# Arduino101.net
KiCad netlist of a schematic drawn in EAGLE
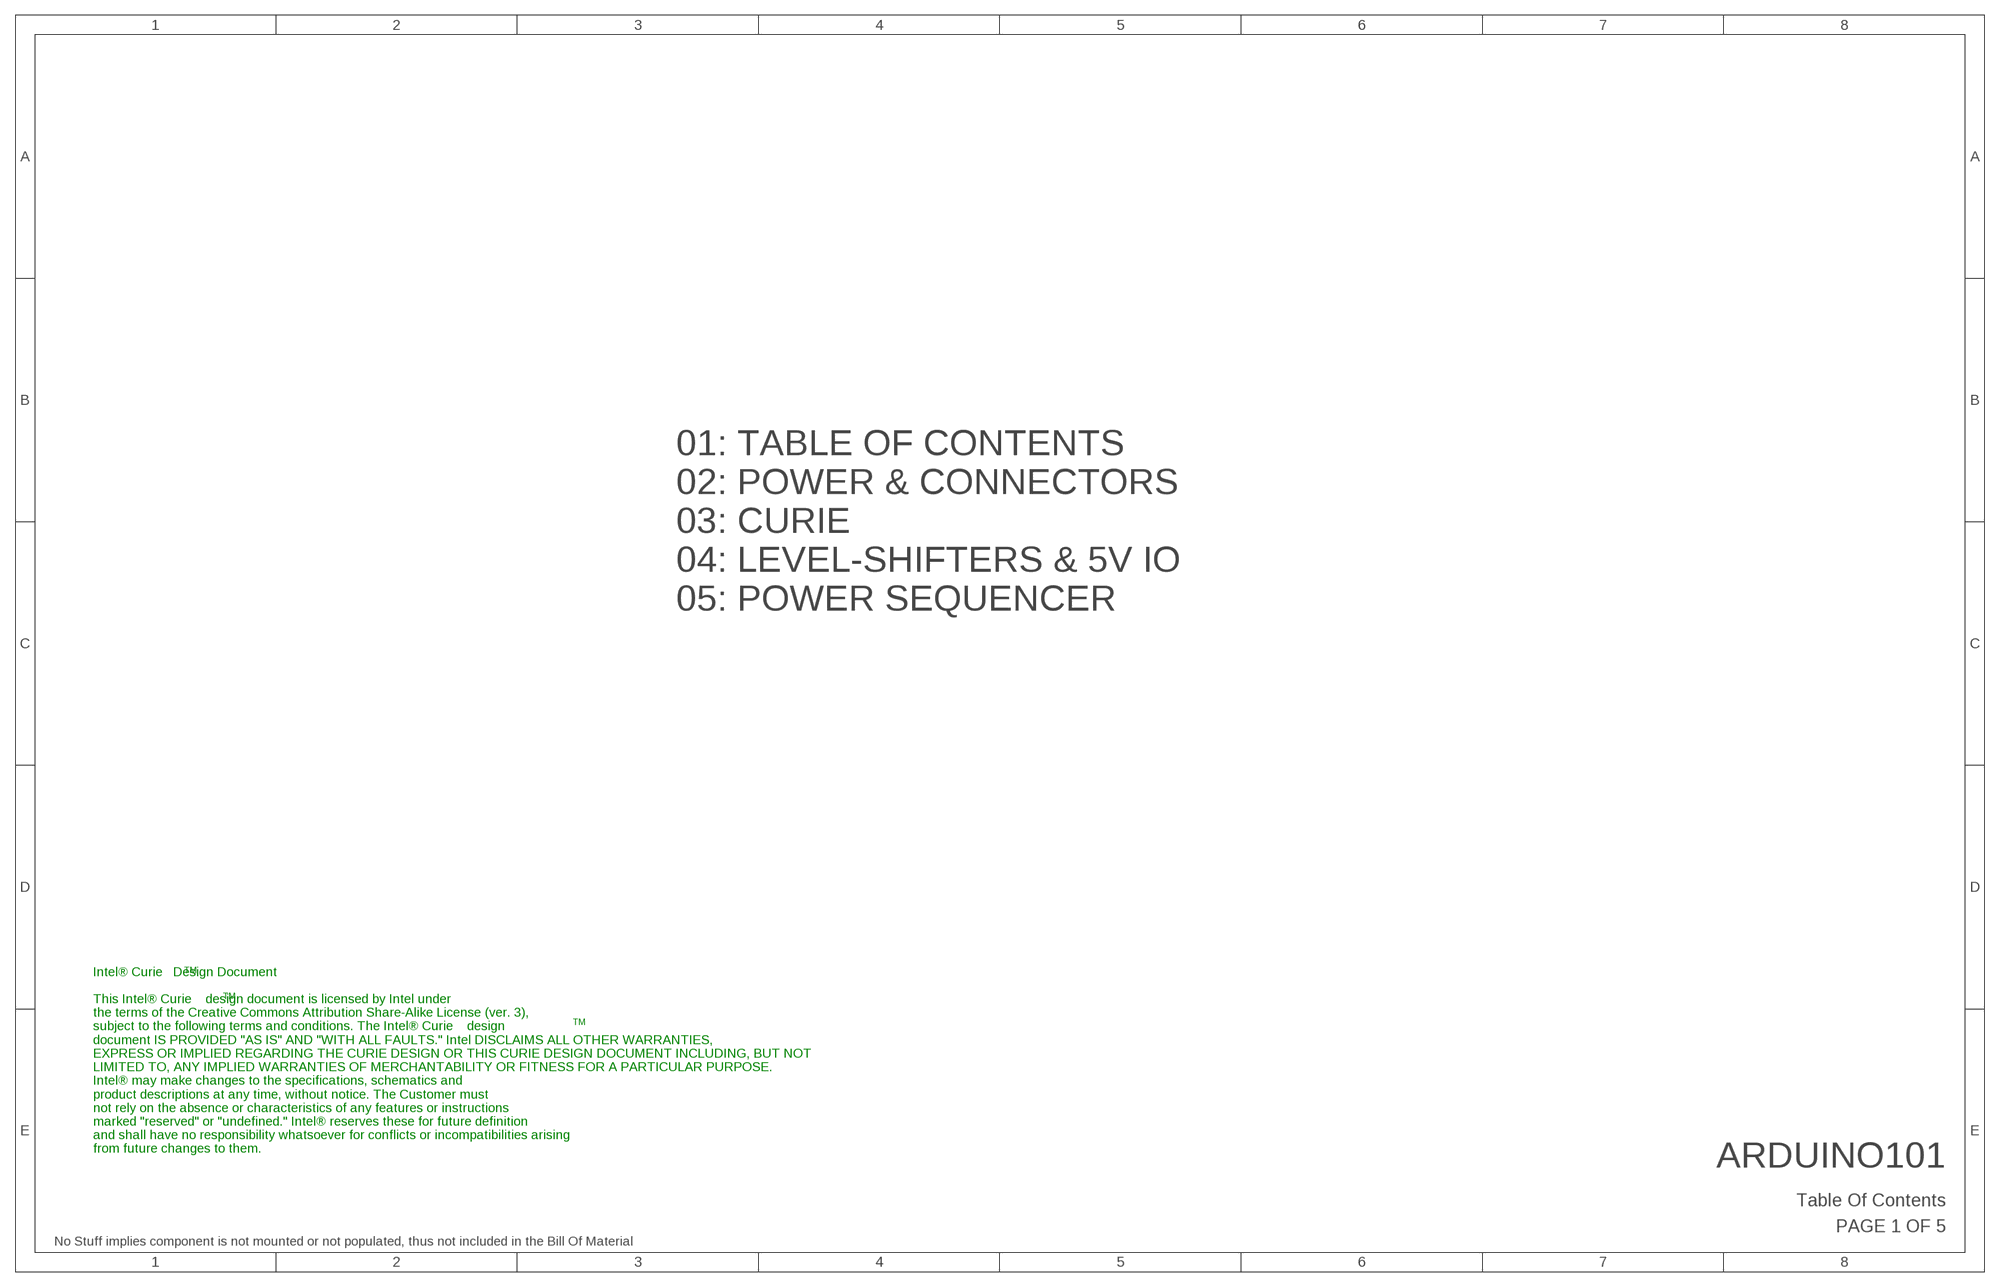
[diagram p0: schematic, sheet 1]
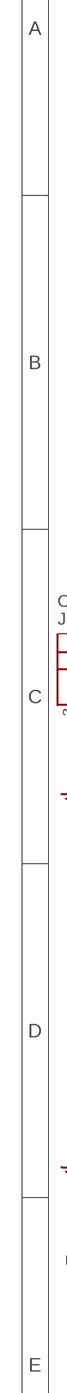
[diagram p1: schematic, sheet 2, part 1 of 2]
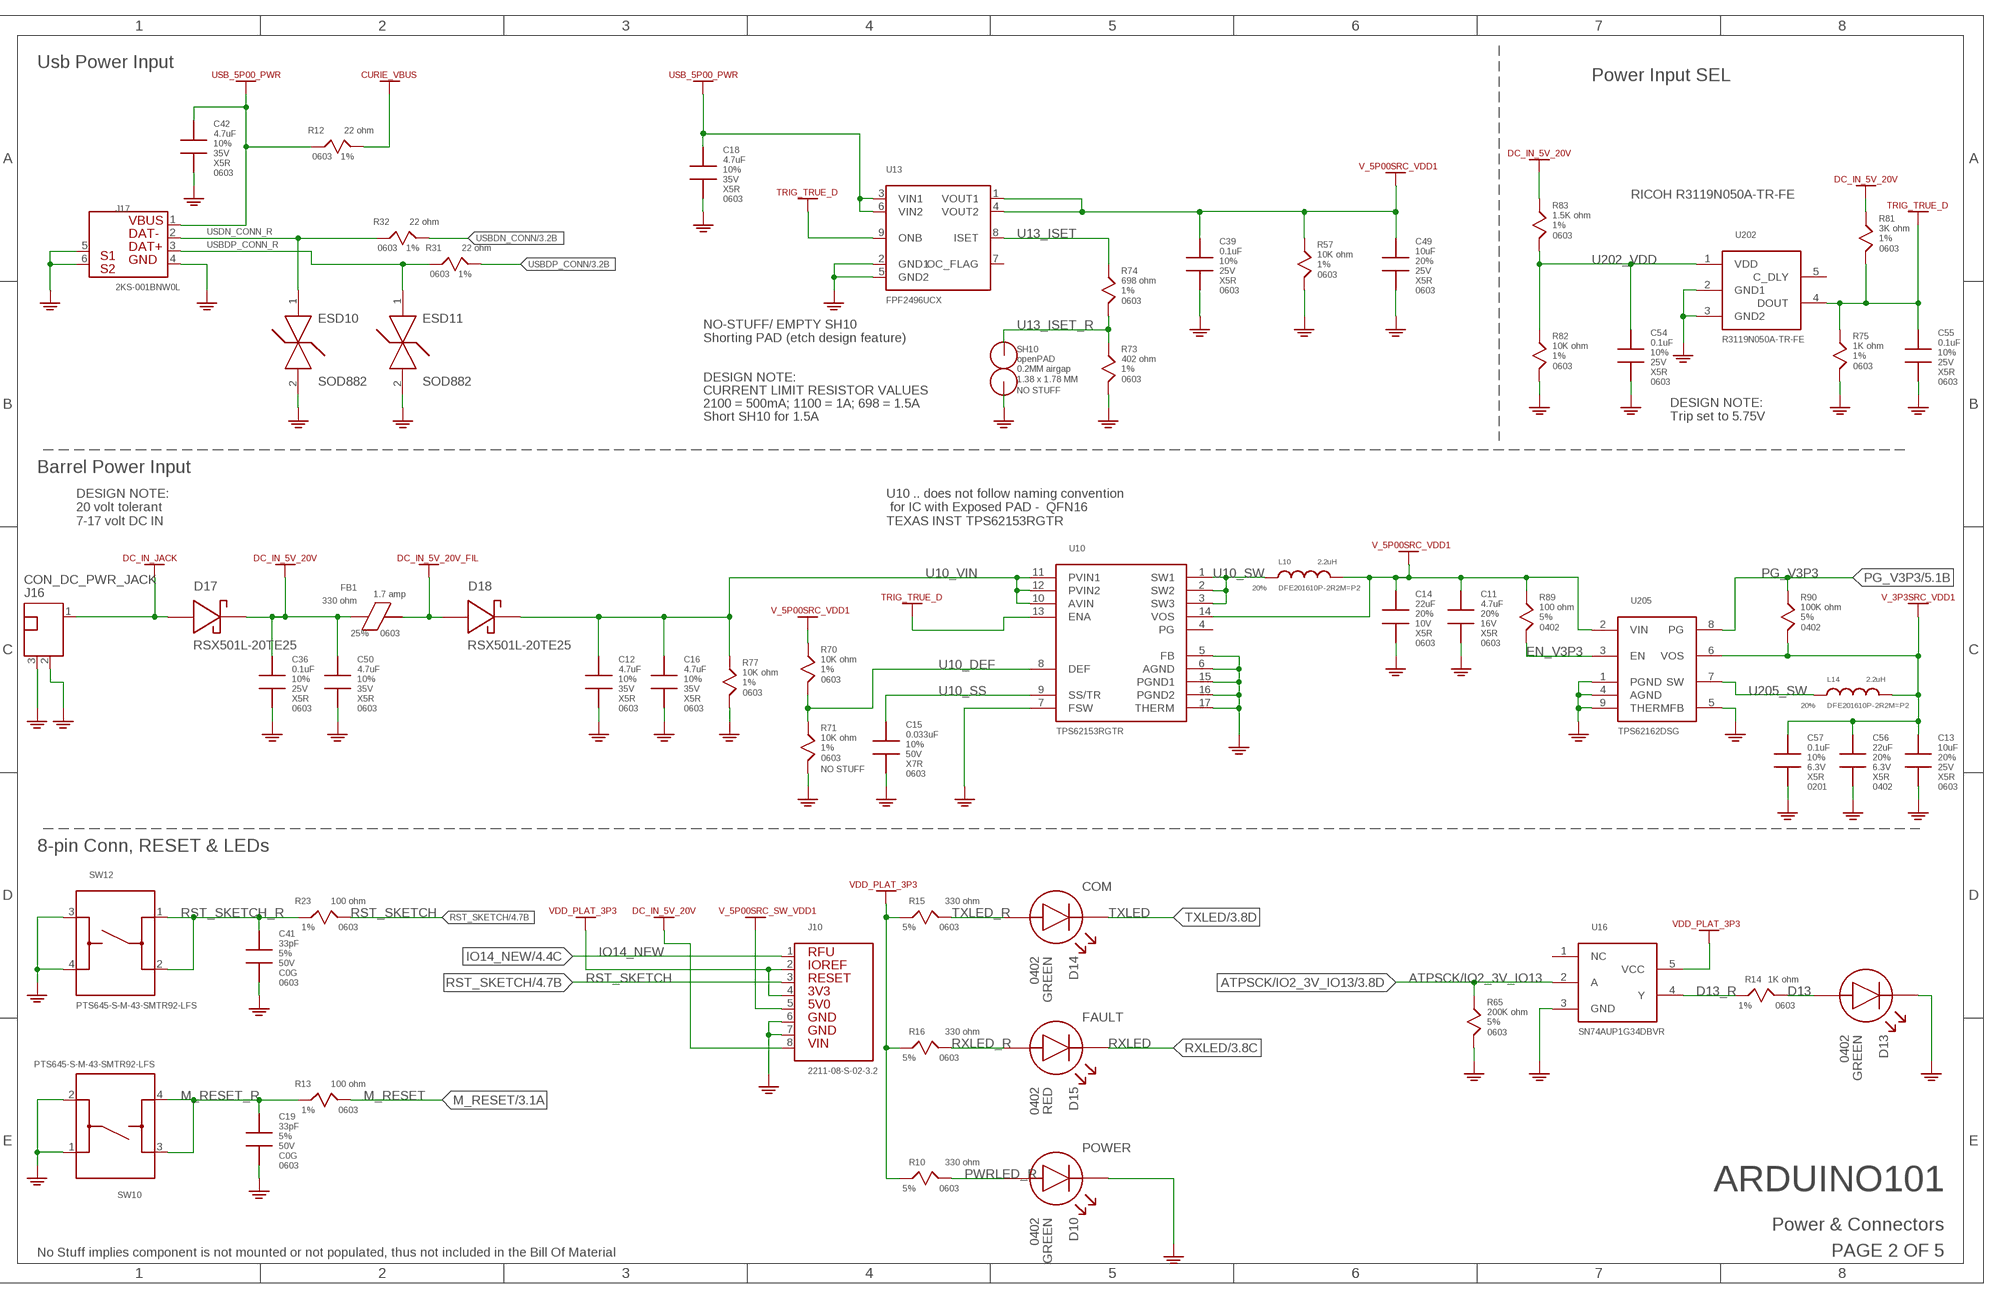
[diagram p2: schematic, sheet 2, part 2 of 2]
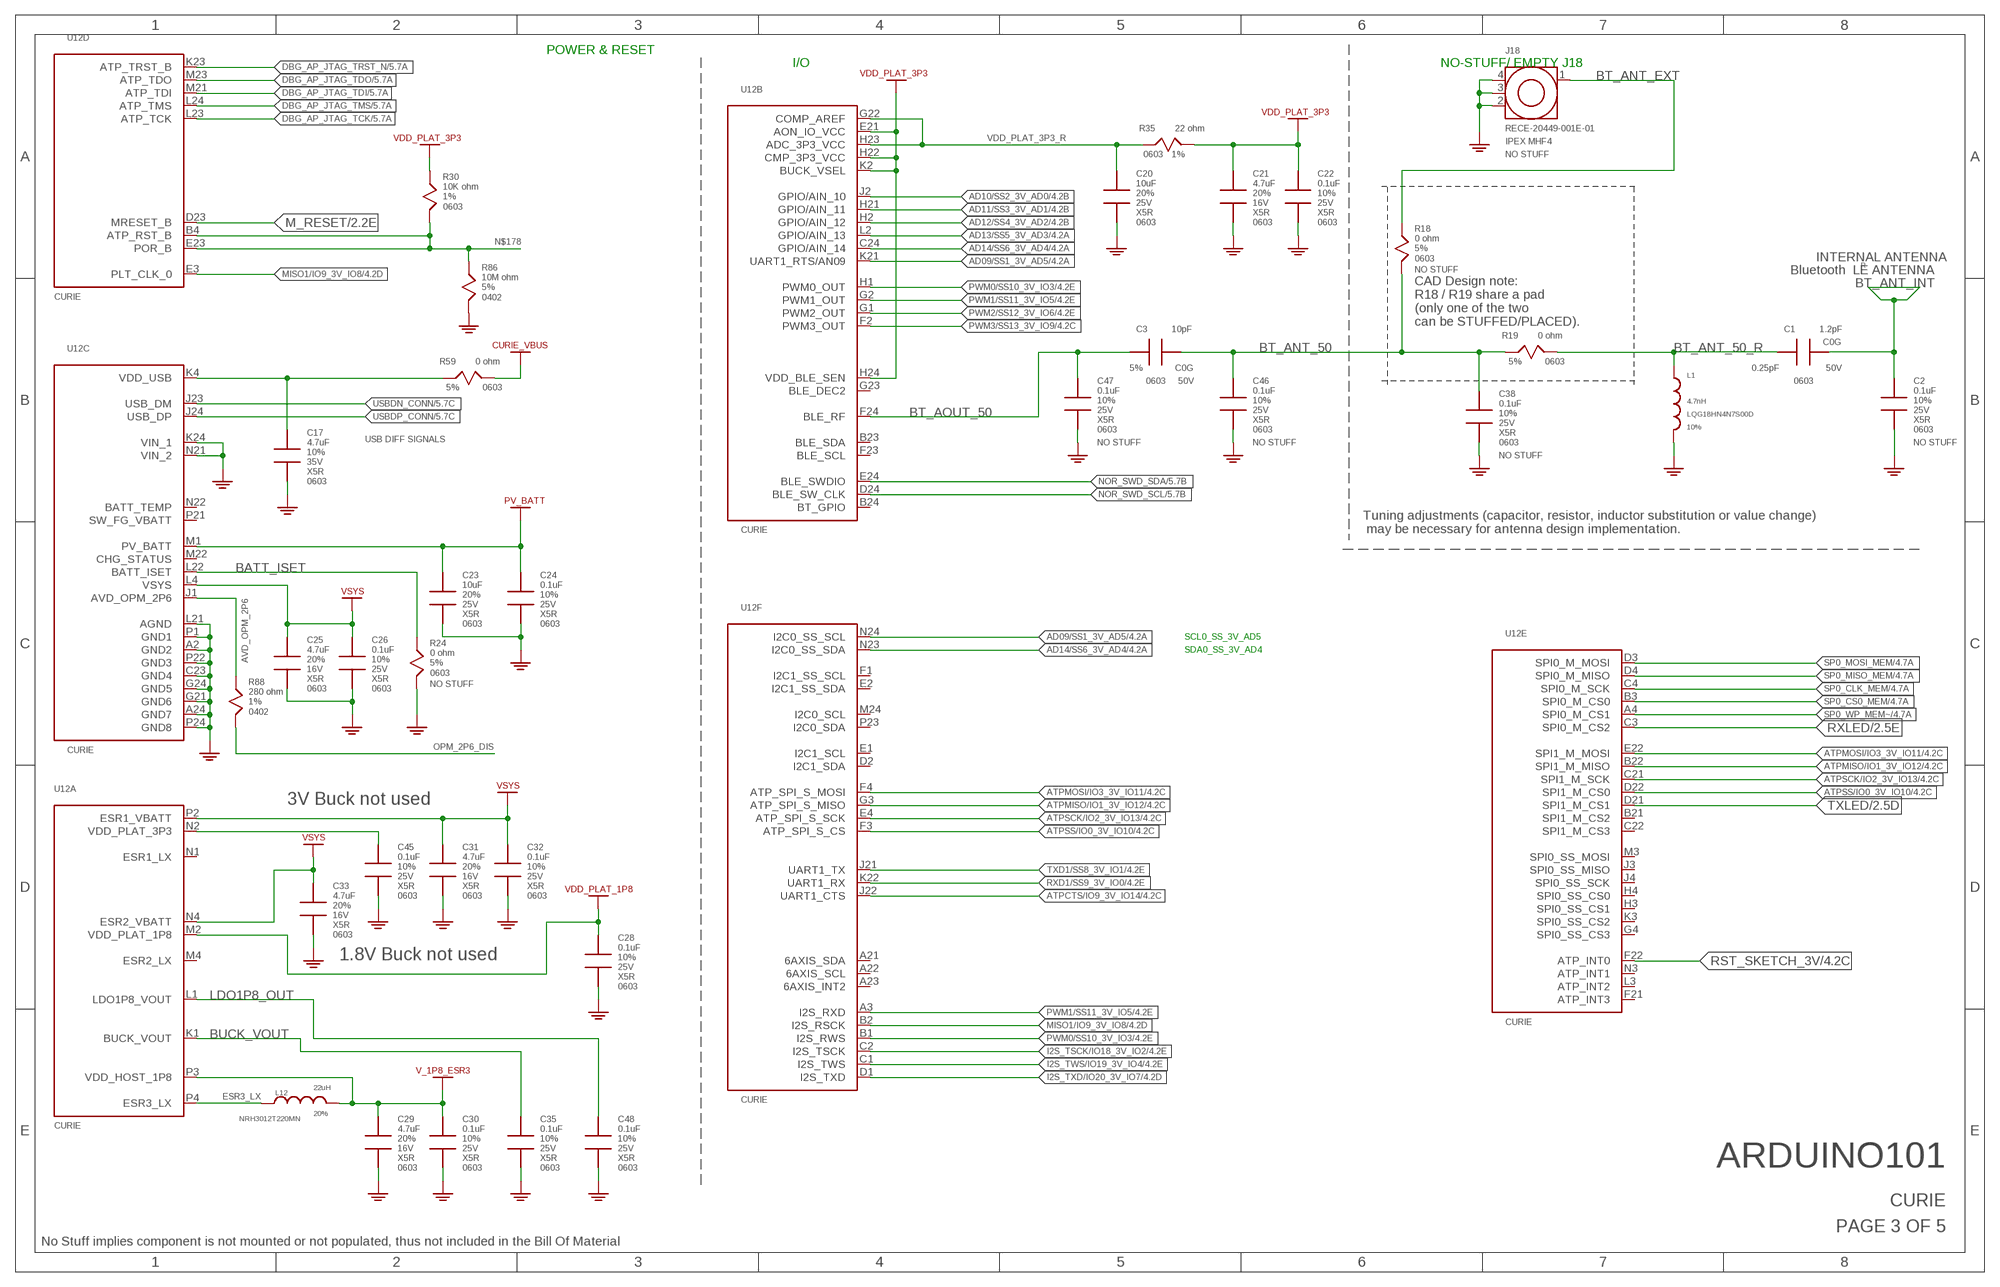
[diagram p3: schematic, sheet 3]
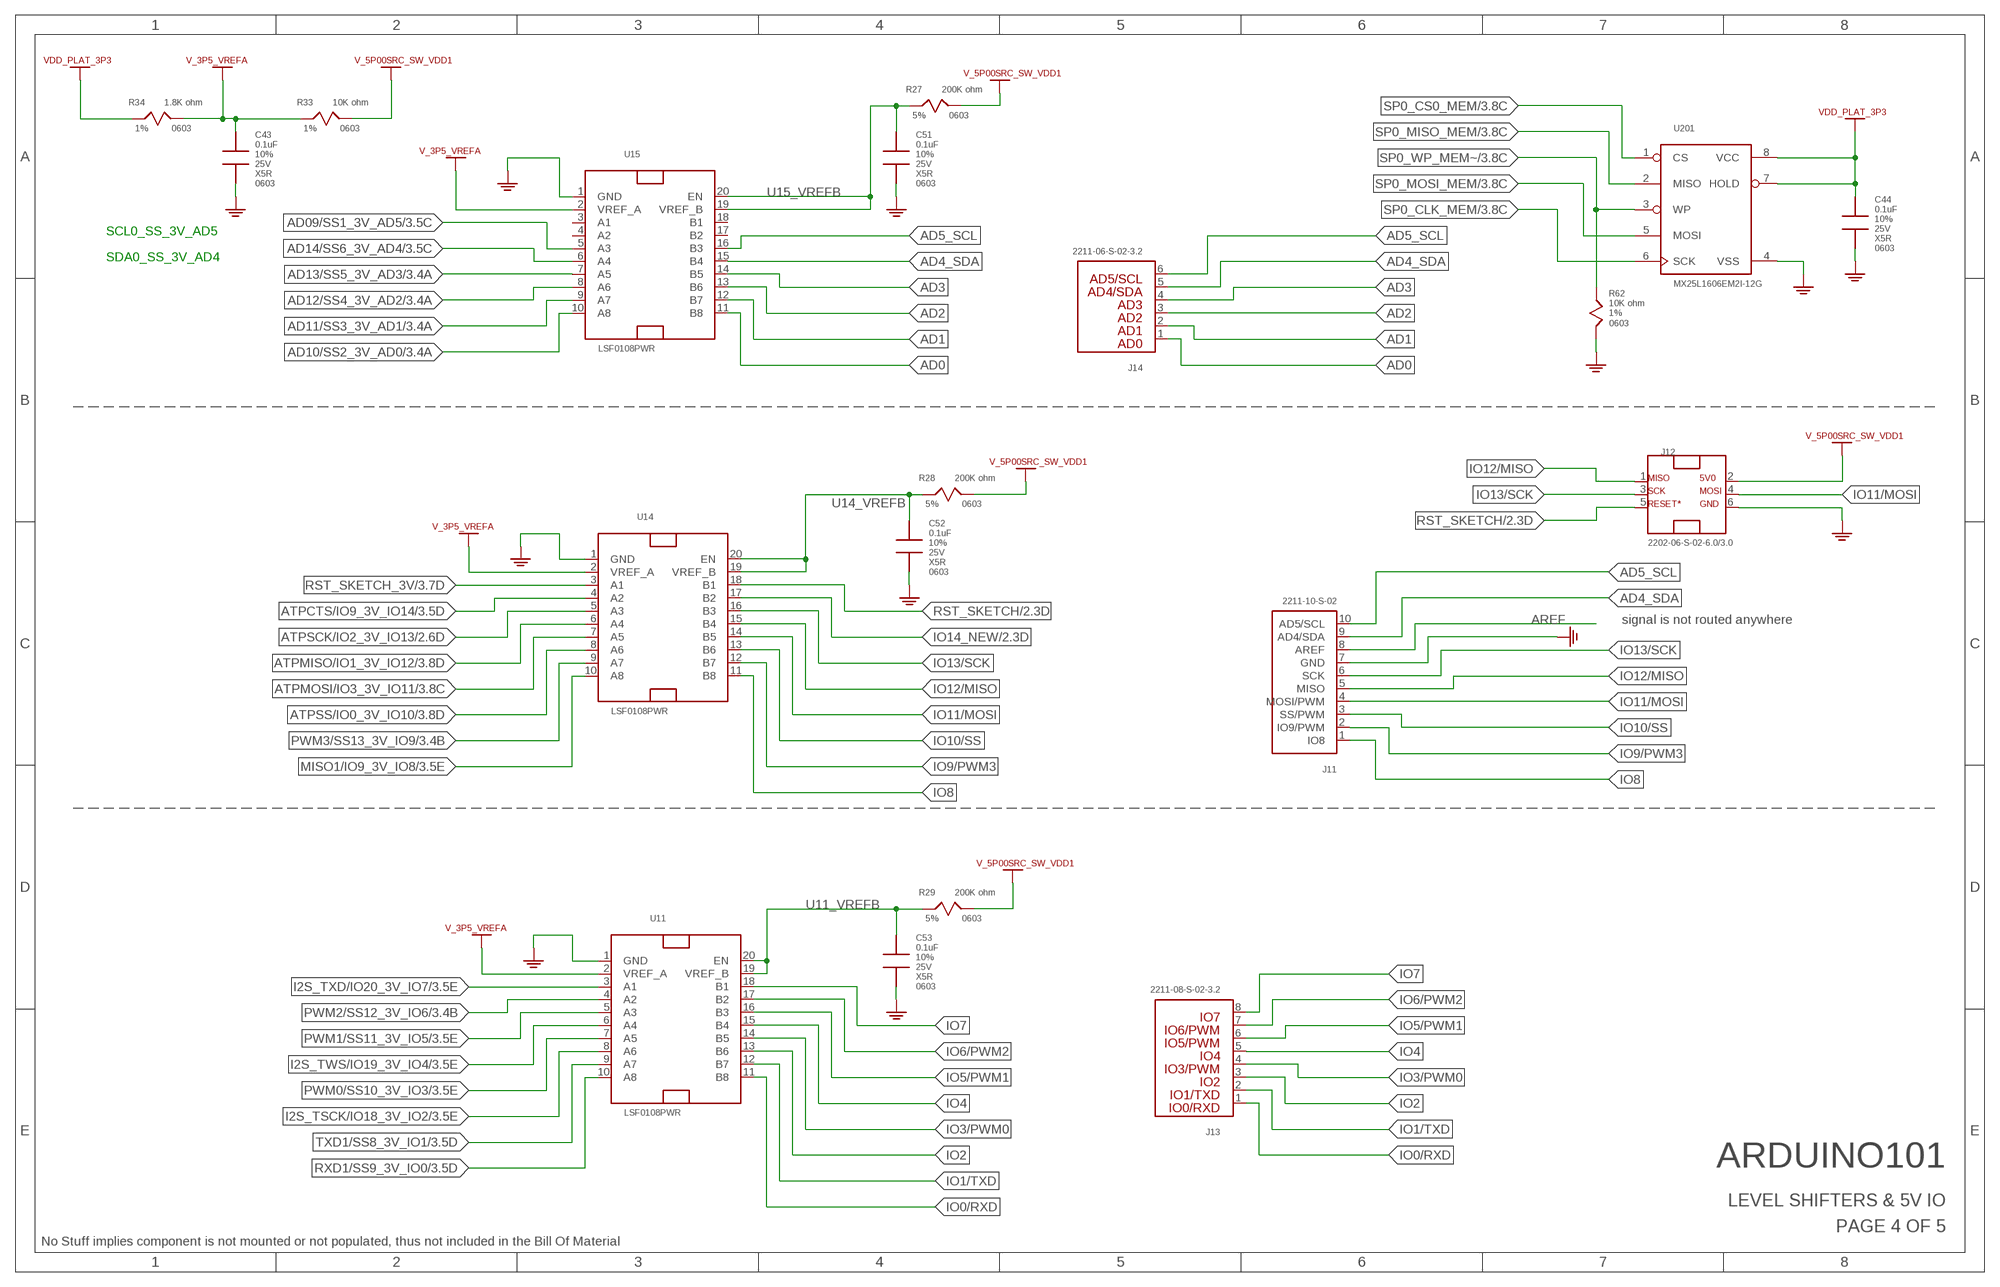
[diagram p4: schematic, sheet 4]
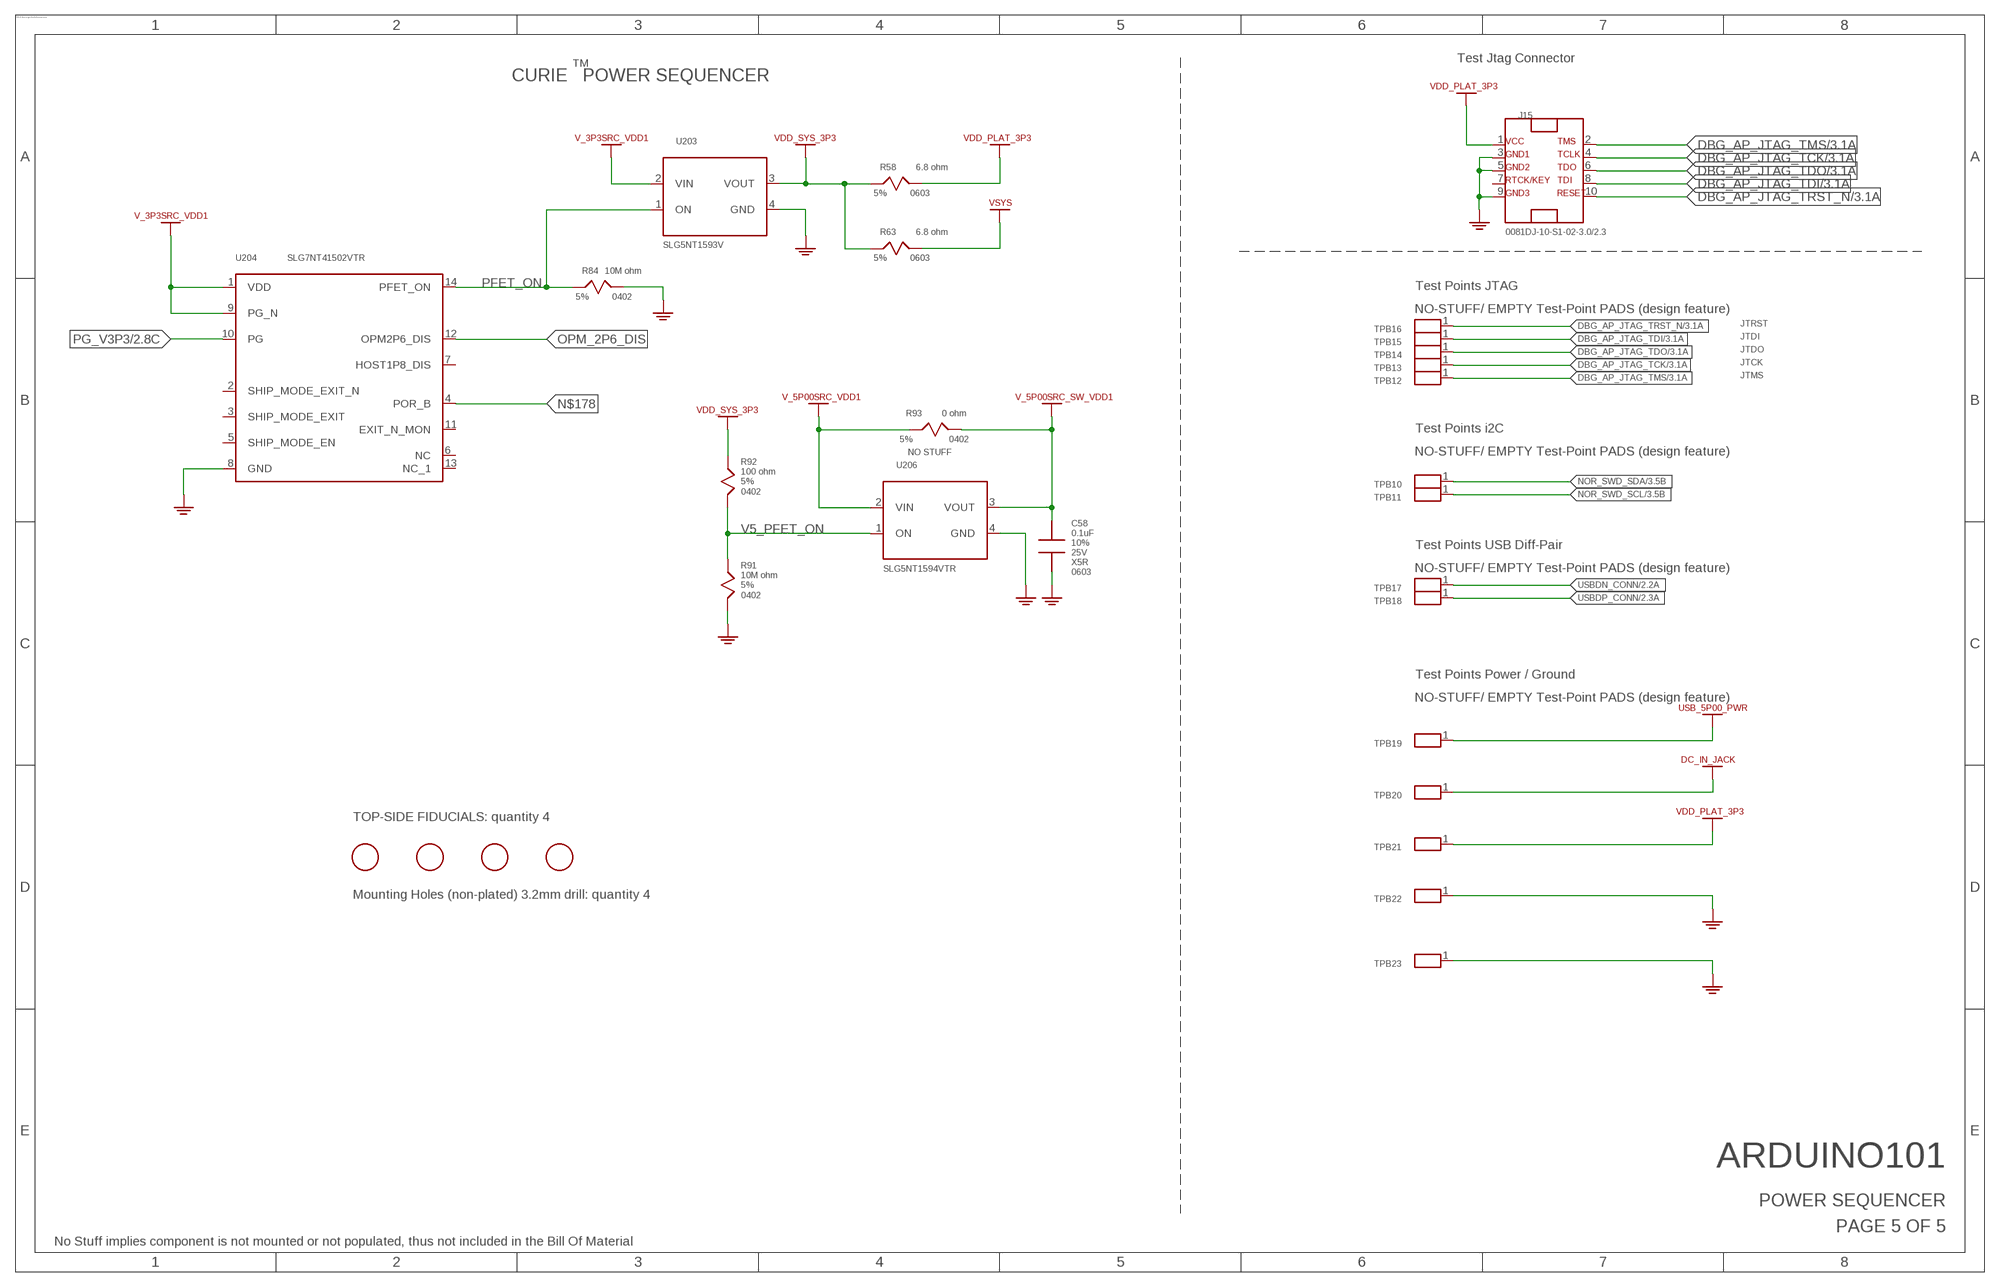
[diagram p5: schematic, sheet 5]

(export (version "E")
  (design (tool "Eeschema 10.0.6"))
  (components
    (comp (ref "C11")
      (value "4.7uF")
      (footprint "eagle-import:0603X90H")
      (fields (field (name "VOLTAGE") "16V") (field (name "MANUFACTURER") "MURATA"))
      (libsource (lib "eagle-import") (part "GRM188R61C475KAAJD"))
    )
    (comp (ref "C12")
      (value "4.7uF")
      (footprint "eagle-import:0603X90H")
      (fields (field (name "VOLTAGE") "35V") (field (name "MANUFACTURER") "MURATA"))
      (libsource (lib "eagle-import") (part "GRM188R6YA475KE15D"))
    )
    (comp (ref "C13")
      (value "10uF")
      (footprint "eagle-import:0603X90H")
      (fields (field (name "VOLTAGE") "25V") (field (name "MANUFACTURER") "MURATA"))
      (libsource (lib "eagle-import") (part "GRM188R61E106MA73D"))
    )
    (comp (ref "C14")
      (value "22uF")
      (footprint "eagle-import:0603X90H")
      (fields (field (name "VOLTAGE") "10V") (field (name "MANUFACTURER") "MURATA"))
      (libsource (lib "eagle-import") (part "GRM188R61A226ME15D"))
    )
    (comp (ref "C15")
      (value "0.033uF")
      (footprint "eagle-import:0603X90H")
      (fields (field (name "VOLTAGE") "50V") (field (name "MANUFACTURER") "MURATA"))
      (libsource (lib "eagle-import") (part "GRM188R71H333KA61F"))
    )
    (comp (ref "C16")
      (value "4.7uF")
      (footprint "eagle-import:0603X90H")
      (fields (field (name "VOLTAGE") "35V") (field (name "MANUFACTURER") "MURATA"))
      (libsource (lib "eagle-import") (part "GRM188R6YA475KE15D"))
    )
    (comp (ref "C18")
      (value "4.7uF")
      (footprint "eagle-import:0603X90H")
      (fields (field (name "VOLTAGE") "35V") (field (name "MANUFACTURER") "MURATA"))
      (libsource (lib "eagle-import") (part "GRM188R6YA475KE15D"))
    )
    (comp (ref "C19")
      (value "33pF")
      (footprint "eagle-import:0603X90H")
      (fields (field (name "VOLTAGE") "50V") (field (name "MANUFACTURER") "MURATA"))
      (libsource (lib "eagle-import") (part "GRM1885C1H330JA01F"))
    )
    (comp (ref "C36")
      (value "0.1uF")
      (footprint "eagle-import:0603X90H")
      (fields (field (name "VOLTAGE") "25V") (field (name "MANUFACTURER") "MURATA"))
      (libsource (lib "eagle-import") (part "GRM188R61E104KA01"))
    )
    (comp (ref "C39")
      (value "0.1uF")
      (footprint "eagle-import:0603X90H")
      (fields (field (name "VOLTAGE") "25V") (field (name "MANUFACTURER") "MURATA"))
      (libsource (lib "eagle-import") (part "GRM188R61E104KA01"))
    )
    (comp (ref "C41")
      (value "33pF")
      (footprint "eagle-import:0603X90H")
      (fields (field (name "VOLTAGE") "50V") (field (name "MANUFACTURER") "MURATA"))
      (libsource (lib "eagle-import") (part "GRM1885C1H330JA01F"))
    )
    (comp (ref "C42")
      (value "4.7uF")
      (footprint "eagle-import:0603X90H")
      (fields (field (name "VOLTAGE") "35V") (field (name "MANUFACTURER") "MURATA"))
      (libsource (lib "eagle-import") (part "GRM188R6YA475KE15D"))
    )
    (comp (ref "C49")
      (value "10uF")
      (footprint "eagle-import:0603X90H")
      (fields (field (name "VOLTAGE") "25V") (field (name "MANUFACTURER") "MURATA"))
      (libsource (lib "eagle-import") (part "GRM188R61E106MA73D"))
    )
    (comp (ref "C50")
      (value "4.7uF")
      (footprint "eagle-import:0603X90H")
      (fields (field (name "VOLTAGE") "35V") (field (name "MANUFACTURER") "MURATA"))
      (libsource (lib "eagle-import") (part "GRM188R6YA475KE15D"))
    )
    (comp (ref "C54")
      (value "0.1uF")
      (footprint "eagle-import:0603X90H")
      (fields (field (name "VOLTAGE") "25V") (field (name "MANUFACTURER") "MURATA"))
      (libsource (lib "eagle-import") (part "GRM188R61E104KA01"))
    )
    (comp (ref "C55")
      (value "0.1uF")
      (footprint "eagle-import:0603X90H")
      (fields (field (name "VOLTAGE") "25V") (field (name "MANUFACTURER") "MURATA"))
      (libsource (lib "eagle-import") (part "GRM188R61E104KA01"))
    )
    (comp (ref "C56")
      (value "22uF")
      (footprint "eagle-import:CAP0402")
      (fields (field (name "VOLTAGE") "6.3V") (field (name "MANUFACTURER") "MURATA"))
      (libsource (lib "eagle-import") (part "GRM155R60J226ME11D"))
    )
    (comp (ref "C57")
      (value "0.1uF")
      (footprint "eagle-import:CAP0201")
      (fields (field (name "VOLTAGE") "6.3V") (field (name "MANUFACTURER") "MURATA"))
      (libsource (lib "eagle-import") (part "GRM033R60J104KE81D"))
    )
    (comp (ref "D10")
      (value "LED_SML-P12PTT86")
      (footprint "eagle-import:LED_100X60X25H_SMLP13")
      (fields (field (name "MANUFACTURER") "ROHM"))
      (libsource (lib "eagle-import") (part "LED_SML-P12PTT86"))
    )
    (comp (ref "D13")
      (value "LED_SML-P12PTT86")
      (footprint "eagle-import:LED_100X60X25H_SMLP13")
      (fields (field (name "MANUFACTURER") "ROHM"))
      (libsource (lib "eagle-import") (part "LED_SML-P12PTT86"))
    )
    (comp (ref "D14")
      (value "LED_SML-P12PTT86")
      (footprint "eagle-import:LED_100X60X25H_SMLP13")
      (fields (field (name "MANUFACTURER") "ROHM"))
      (libsource (lib "eagle-import") (part "LED_SML-P12PTT86"))
    )
    (comp (ref "D15")
      (value "LED_SML-P11UTT86")
      (footprint "eagle-import:LED_100X60X25H_SMLP13")
      (fields (field (name "MANUFACTURER") "ROHM"))
      (libsource (lib "eagle-import") (part "LED_SML-P11UTT86"))
    )
    (comp (ref "D17")
      (value "DIO_RSX501L-20TE25")
      (footprint "eagle-import:DIO2_450X260X220H")
      (fields (field (name "MANUFACTURER") "ROHM CO"))
      (libsource (lib "eagle-import") (part "DIO_RSX501L-20TE25"))
    )
    (comp (ref "D18")
      (value "DIO_RSX501L-20TE25")
      (footprint "eagle-import:DIO2_450X260X220H")
      (fields (field (name "MANUFACTURER") "ROHM CO"))
      (libsource (lib "eagle-import") (part "DIO_RSX501L-20TE25"))
    )
    (comp (ref "ESD10")
      (value "PESD5V0X1BCAL,315")
      (footprint "eagle-import:DIO_SOD882")
      (fields (field (name "MANUFACTURER") "NXP Semiconductors"))
      (libsource (lib "eagle-import") (part "PESD5V0X1BCAL,315"))
    )
    (comp (ref "ESD11")
      (value "PESD5V0X1BCAL,315")
      (footprint "eagle-import:DIO_SOD882")
      (fields (field (name "MANUFACTURER") "NXP Semiconductors"))
      (libsource (lib "eagle-import") (part "PESD5V0X1BCAL,315"))
    )
    (comp (ref "FB1")
      (value "FERRITE_BEAD_0603_BLM18KG331SN1D")
      (footprint "eagle-import:0603X90H")
      (fields
        (field (name "TOL") "25%")
        (field (name "IMPEDANCE") "330 ohm")
        (field (name "SIZE") "0603")
        (field (name "MANUFACTURER") "MURATA")
      )
      (libsource (lib "eagle-import") (part "FERRITE_BEAD_0603_BLM18KG331SN1D"))
    )
    (comp (ref "J10")
      (value "CON_1X8_2211-08-S-02-3.2")
      (footprint "eagle-import:CONF1X8-254P_2104X240X850H_TH")
      (fields (field (name "MANUFACTURER") "SINGATRON"))
      (libsource (lib "eagle-import") (part "CON_1X8_2211-08-S-02-3.2"))
    )
    (comp (ref "J16")
      (value "CON_DC_PWR_JACK")
      (footprint "eagle-import:CON_JACK_880X1350X1135H_EJ508A")
      (fields (field (name "MANUFACTURER") "SINGATRON"))
      (libsource (lib "eagle-import") (part "CON_DC_PWR_JACK"))
    )
    (comp (ref "J17")
      (value "CON_USB_TYPE_B")
      (footprint "eagle-import:CON_USB_1204X1650X1115_AUY1007")
      (fields (field (name "MANUFACTURER") "SINGATRON"))
      (libsource (lib "eagle-import") (part "CON_USB_TYPE_B"))
    )
    (comp (ref "L10")
      (value "2.2uH")
      (footprint "eagle-import:0806X100H")
      (fields
        (field (name "PN") "DFE201610P-2R2M=P2")
        (field (name "TOL") "20%")
        (field (name "MANUFACTURER") "MURATA")
      )
      (libsource (lib "eagle-import") (part "IND_DFE201610P-2R2M=P2"))
    )
    (comp (ref "L14")
      (value "2.2uH")
      (footprint "eagle-import:0806X100H")
      (fields
        (field (name "PN") "DFE201610P-2R2M=P2")
        (field (name "TOL") "20%")
        (field (name "MANUFACTURER") "MURATA")
      )
      (libsource (lib "eagle-import") (part "IND_DFE201610P-2R2M=P2"))
    )
    (comp (ref "R10")
      (value "330 ohm")
      (footprint "eagle-import:0603X90H")
      (fields
        (field (name "TOL") "5%")
        (field (name "SIZE") "0603")
        (field (name "MANUFACTURER") "KOA SPEER")
      )
      (libsource (lib "eagle-import") (part "RK73B1JTTD331J"))
    )
    (comp (ref "R12")
      (value "22 ohm")
      (footprint "eagle-import:0603X90H")
      (fields
        (field (name "TOL") "1%")
        (field (name "SIZE") "0603")
        (field (name "MANUFACTURER") "VISHAY-DALE")
      )
      (libsource (lib "eagle-import") (part "CRCW060322R0FKEA"))
    )
    (comp (ref "R13")
      (value "100 ohm")
      (footprint "eagle-import:0603X90H")
      (fields
        (field (name "TOL") "1%")
        (field (name "SIZE") "0603")
        (field (name "MANUFACTURER") "KOA SPEER")
      )
      (libsource (lib "eagle-import") (part "RK73H1JTTD1000F"))
    )
    (comp (ref "R14")
      (value "1K ohm")
      (footprint "eagle-import:0603X90H")
      (fields
        (field (name "TOL") "1%")
        (field (name "SIZE") "0603")
        (field (name "MANUFACTURER") "KOA SPEER")
      )
      (libsource (lib "eagle-import") (part "RK73H1JTTD1001F"))
    )
    (comp (ref "R15")
      (value "330 ohm")
      (footprint "eagle-import:0603X90H")
      (fields
        (field (name "TOL") "5%")
        (field (name "SIZE") "0603")
        (field (name "MANUFACTURER") "KOA SPEER")
      )
      (libsource (lib "eagle-import") (part "RK73B1JTTD331J"))
    )
    (comp (ref "R16")
      (value "330 ohm")
      (footprint "eagle-import:0603X90H")
      (fields
        (field (name "TOL") "5%")
        (field (name "SIZE") "0603")
        (field (name "MANUFACTURER") "KOA SPEER")
      )
      (libsource (lib "eagle-import") (part "RK73B1JTTD331J"))
    )
    (comp (ref "R23")
      (value "100 ohm")
      (footprint "eagle-import:0603X90H")
      (fields
        (field (name "TOL") "1%")
        (field (name "SIZE") "0603")
        (field (name "MANUFACTURER") "KOA SPEER")
      )
      (libsource (lib "eagle-import") (part "RK73H1JTTD1000F"))
    )
    (comp (ref "R31")
      (value "22 ohm")
      (footprint "eagle-import:0603X90H")
      (fields
        (field (name "TOL") "1%")
        (field (name "SIZE") "0603")
        (field (name "MANUFACTURER") "VISHAY-DALE")
      )
      (libsource (lib "eagle-import") (part "CRCW060322R0FKEA"))
    )
    (comp (ref "R32")
      (value "22 ohm")
      (footprint "eagle-import:0603X90H")
      (fields
        (field (name "TOL") "1%")
        (field (name "SIZE") "0603")
        (field (name "MANUFACTURER") "VISHAY-DALE")
      )
      (libsource (lib "eagle-import") (part "CRCW060322R0FKEA"))
    )
    (comp (ref "R57")
      (value "10K ohm")
      (footprint "eagle-import:0603X90H")
      (fields (field (name "MANUFACTURER") "VISHAY-DALE"))
      (libsource (lib "eagle-import") (part "CRCW060310K0FKEA"))
    )
    (comp (ref "R65")
      (value "200K ohm")
      (footprint "eagle-import:0603X90H")
      (fields (field (name "MANUFACTURER") "VISHAY-DALE"))
      (libsource (lib "eagle-import") (part "CRCW0603200KJNEB"))
    )
    (comp (ref "R70")
      (value "10K ohm")
      (footprint "eagle-import:0603X90H")
      (fields (field (name "MANUFACTURER") "VISHAY-DALE"))
      (libsource (lib "eagle-import") (part "CRCW060310K0FKEA"))
    )
    (comp (ref "R71")
      (value "10K ohm")
      (footprint "eagle-import:0603X90H")
      (fields (field (name "MANUFACTURER") "VISHAY-DALE"))
      (libsource (lib "eagle-import") (part "CRCW060310K0FKEA_NOSTUFF"))
    )
    (comp (ref "R73")
      (value "402 ohm")
      (footprint "eagle-import:0603X90H")
      (fields (field (name "MANUFACTURER") "VISHAY-DALE"))
      (libsource (lib "eagle-import") (part "CRCW0603402RFKEB"))
    )
    (comp (ref "R74")
      (value "698 ohm")
      (footprint "eagle-import:0603X90H")
      (fields (field (name "MANUFACTURER") "VISHAY-DALE"))
      (libsource (lib "eagle-import") (part "CRCW0603698RFKEB"))
    )
    (comp (ref "R75")
      (value "1K ohm")
      (footprint "eagle-import:0603X90H")
      (fields (field (name "MANUFACTURER") "KOA SPEER"))
      (libsource (lib "eagle-import") (part "RK73H1JTTD1001F"))
    )
    (comp (ref "R77")
      (value "10K ohm")
      (footprint "eagle-import:0603X90H")
      (fields (field (name "MANUFACTURER") "VISHAY-DALE"))
      (libsource (lib "eagle-import") (part "CRCW060310K0FKEA"))
    )
    (comp (ref "R81")
      (value "3K ohm")
      (footprint "eagle-import:0603X90H")
      (fields (field (name "MANUFACTURER") "KOA SPEER"))
      (libsource (lib "eagle-import") (part "RK73H1JTTD3001F"))
    )
    (comp (ref "R82")
      (value "10K ohm")
      (footprint "eagle-import:0603X90H")
      (fields (field (name "MANUFACTURER") "VISHAY-DALE"))
      (libsource (lib "eagle-import") (part "CRCW060310K0FKEA"))
    )
    (comp (ref "R83")
      (value "1.5K ohm")
      (footprint "eagle-import:0603X90H")
      (fields (field (name "MANUFACTURER") "VISHAY-DALE"))
      (libsource (lib "eagle-import") (part "CRCW06031K50FKEB"))
    )
    (comp (ref "R89")
      (value "100 ohm")
      (footprint "eagle-import:SMR0402")
      (fields (field (name "MANUFACTURER") "VISHAY-DALE"))
      (libsource (lib "eagle-import") (part "CRCW0402100RJNED"))
    )
    (comp (ref "R90")
      (value "100K ohm")
      (footprint "eagle-import:SMR0402")
      (fields (field (name "MANUFACTURER") "KOA SPEER"))
      (libsource (lib "eagle-import") (part "RK73B1ETTP104J"))
    )
    (comp (ref "SH10")
      (value "openPAD")
      (footprint "eagle-import:SHORT_140X180")
      (fields (field (name "MANUFACTURER") "PCB"))
      (libsource (lib "eagle-import") (part "SHORTING_PAD_2_SHORT_140X180_SH"))
    )
    (comp (ref "SW10")
      (value "SWITCH_PTS645-S-M-43-SMTR92-LFS")
      (footprint "eagle-import:SW4_600X600X430H_SM_PTS645")
      (fields (field (name "MANUFACTURER") "C&K COMPONENTS"))
      (libsource (lib "eagle-import") (part "SWITCH_PTS645-S-M-43-SMTR92-LFS"))
    )
    (comp (ref "SW12")
      (value "SWITCH_PTS645-S-M-43-SMTR92-LFS")
      (footprint "eagle-import:SW4_600X600X430H_SM_PTS645")
      (fields (field (name "MANUFACTURER") "C&K COMPONENTS"))
      (libsource (lib "eagle-import") (part "SWITCH_PTS645-S-M-43-SMTR92-LFS"))
    )
    (comp (ref "U10")
      (value "TPS62153RGTR")
      (footprint "eagle-import:QFN16-50P_300X300X100H_TR")
      (fields (field (name "MANUFACTURER") "TEXAS INSTRUMENTS"))
      (libsource (lib "eagle-import") (part "TPS62153RGTR"))
    )
    (comp (ref "U13")
      (value "FPF2496UCX_WLCSP_VREG")
      (footprint "eagle-import:BGA9_3X3-40P_121X121X63H")
      (fields (field (name "MANUFACTURER") "FAIRCHILD SEMI"))
      (libsource (lib "eagle-import") (part "FPF2496UCX_WLCSP_VREG"))
    )
    (comp (ref "U16")
      (value "SN74AUP1G34DBVR")
      (footprint "eagle-import:SOT23-5_160X290X145H")
      (fields (field (name "MANUFACTURER") "TEXAS INSTRUMENTS"))
      (libsource (lib "eagle-import") (part "SN74AUP1G34DBVR"))
    )
    (comp (ref "U202")
      (value "R3119-VREG")
      (footprint "eagle-import:SOT23-5_160X290X120H")
      (fields (field (name "MANUFACTURER") "RICOH"))
      (libsource (lib "eagle-import") (part "R3119-VREG"))
    )
    (comp (ref "U205")
      (value "TPS62162DSG")
      (footprint "eagle-import:USON8_5MM_2X2MM-DIE")
      (fields (field (name "MANUFACTURER") "TEXAS INSTRUMENTS"))
      (libsource (lib "eagle-import") (part "TPS62162DSG"))
    )
    (comp (ref "C58")
      (value "0.1uF")
      (footprint "eagle-import:0603X90H")
      (fields (field (name "VOLTAGE") "25V") (field (name "MANUFACTURER") "MURATA"))
      (libsource (lib "eagle-import") (part "GRM188R61E104KA01"))
    )
    (comp (ref "J15")
      (value "CON_JTAG_20021111-00010T4LF")
      (footprint "eagle-import:CONM2X5-127P_1270X559X533H")
      (fields (field (name "MANUFACTURER") "SINGATRON"))
      (libsource (lib "eagle-import") (part "CON_JTAG_20021111-00010T4LF"))
    )
    (comp (ref "R58")
      (value "6.8 ohm")
      (footprint "eagle-import:0603X90H")
      (fields
        (field (name "TOL") "5%")
        (field (name "SIZE") "0603")
        (field (name "MANUFACTURER") "VISHAY-DALE")
      )
      (libsource (lib "eagle-import") (part "CRCW06036R80JNEB"))
    )
    (comp (ref "R63")
      (value "6.8 ohm")
      (footprint "eagle-import:0603X90H")
      (fields
        (field (name "TOL") "5%")
        (field (name "SIZE") "0603")
        (field (name "MANUFACTURER") "VISHAY-DALE")
      )
      (libsource (lib "eagle-import") (part "CRCW06036R80JNEB"))
    )
    (comp (ref "R84")
      (value "10M ohm")
      (footprint "eagle-import:SMR0402")
      (fields
        (field (name "TOL") "5%")
        (field (name "SIZE") "0402")
        (field (name "MANUFACTURER") "KOA SPEER")
      )
      (libsource (lib "eagle-import") (part "RK73B1ETTP106J"))
    )
    (comp (ref "R91")
      (value "10M ohm")
      (footprint "eagle-import:SMR0402")
      (fields (field (name "MANUFACTURER") "KOA SPEER"))
      (libsource (lib "eagle-import") (part "RK73B1ETTP106J"))
    )
    (comp (ref "R92")
      (value "100 ohm")
      (footprint "eagle-import:SMR0402")
      (fields (field (name "MANUFACTURER") "VISHAY-DALE"))
      (libsource (lib "eagle-import") (part "CRCW0402100RJNED"))
    )
    (comp (ref "R93")
      (value "0 ohm")
      (footprint "eagle-import:SMR0402")
      (fields
        (field (name "TOL") "5%")
        (field (name "SIZE") "0402")
        (field (name "STUFF") "NO STUFF")
        (field (name "MANUFACTURER") "VISHAY-DALE")
      )
      (libsource (lib "eagle-import") (part "CRCW04020000Z0ED_NOSTUFF"))
    )
    (comp (ref "TPB10")
      (value "TESTPAD")
      (footprint "eagle-import:TP40")
      (libsource (lib "eagle-import") (part "TESTPAD"))
    )
    (comp (ref "TPB11")
      (value "TESTPAD")
      (footprint "eagle-import:TP40")
      (libsource (lib "eagle-import") (part "TESTPAD"))
    )
    (comp (ref "TPB12")
      (value "TESTPAD")
      (footprint "eagle-import:TP40")
      (libsource (lib "eagle-import") (part "TESTPAD"))
    )
    (comp (ref "TPB13")
      (value "TESTPAD")
      (footprint "eagle-import:TP40")
      (libsource (lib "eagle-import") (part "TESTPAD"))
    )
    (comp (ref "TPB14")
      (value "TESTPAD")
      (footprint "eagle-import:TP40")
      (libsource (lib "eagle-import") (part "TESTPAD"))
    )
    (comp (ref "TPB15")
      (value "TESTPAD")
      (footprint "eagle-import:TP40")
      (libsource (lib "eagle-import") (part "TESTPAD"))
    )
    (comp (ref "TPB16")
      (value "TESTPAD")
      (footprint "eagle-import:TP40")
      (libsource (lib "eagle-import") (part "TESTPAD"))
    )
    (comp (ref "TPB17")
      (value "TESTPAD")
      (footprint "eagle-import:TP40")
      (libsource (lib "eagle-import") (part "TESTPAD"))
    )
    (comp (ref "TPB18")
      (value "TESTPAD")
      (footprint "eagle-import:TP40")
      (libsource (lib "eagle-import") (part "TESTPAD"))
    )
    (comp (ref "TPB19")
      (value "TESTPAD")
      (footprint "eagle-import:TP40")
      (libsource (lib "eagle-import") (part "TESTPAD"))
    )
    (comp (ref "TPB20")
      (value "TESTPAD")
      (footprint "eagle-import:TP40")
      (libsource (lib "eagle-import") (part "TESTPAD"))
    )
    (comp (ref "TPB21")
      (value "TESTPAD")
      (footprint "eagle-import:TP40")
      (libsource (lib "eagle-import") (part "TESTPAD"))
    )
    (comp (ref "TPB22")
      (value "TESTPAD")
      (footprint "eagle-import:TP40")
      (libsource (lib "eagle-import") (part "TESTPAD"))
    )
    (comp (ref "TPB23")
      (value "TESTPAD")
      (footprint "eagle-import:TP40")
      (libsource (lib "eagle-import") (part "TESTPAD"))
    )
    (comp (ref "U$1")
      (value "FIDUCIAL_40")
      (footprint "eagle-import:FIDUCIAL_40")
      (libsource (lib "eagle-import") (part "FIDUCIAL_40"))
    )
    (comp (ref "U$2")
      (value "FIDUCIAL_40")
      (footprint "eagle-import:FIDUCIAL_40")
      (libsource (lib "eagle-import") (part "FIDUCIAL_40"))
    )
    (comp (ref "U$3")
      (value "FIDUCIAL_40")
      (footprint "eagle-import:FIDUCIAL_40")
      (libsource (lib "eagle-import") (part "FIDUCIAL_40"))
    )
    (comp (ref "U$4")
      (value "FIDUCIAL_40")
      (footprint "eagle-import:FIDUCIAL_40")
      (libsource (lib "eagle-import") (part "FIDUCIAL_40"))
    )
    (comp (ref "U203")
      (value "SLG5NT1593V")
      (footprint "eagle-import:LCC4_P4MM_SQ1MM")
      (libsource (lib "eagle-import") (part "SLG5NT1593V"))
    )
    (comp (ref "U204")
      (value "SLG7NT41502VTR")
      (footprint "eagle-import:STQFN14_2_40MA")
      (fields (field (name "MANUFACTURER") "SILEGO"))
      (libsource (lib "eagle-import") (part "SLG7NT41502VTR"))
    )
    (comp (ref "U206")
      (value "SLG5NT15944V")
      (footprint "eagle-import:LCC4_P4MM_SQ1MM")
      (fields (field (name "MANUFACTURER") "SILEGO"))
      (libsource (lib "eagle-import") (part "SLG5NT15944V"))
    )
    (comp (ref "C43")
      (value "0.1uF")
      (footprint "eagle-import:0603X90H")
      (fields (field (name "VOLTAGE") "25V") (field (name "MANUFACTURER") "MURATA"))
      (libsource (lib "eagle-import") (part "GRM188R61E104KA01"))
    )
    (comp (ref "C44")
      (value "0.1uF")
      (footprint "eagle-import:0603X90H")
      (fields (field (name "VOLTAGE") "25V") (field (name "MANUFACTURER") "MURATA"))
      (libsource (lib "eagle-import") (part "GRM188R61E104KA01"))
    )
    (comp (ref "C51")
      (value "0.1uF")
      (footprint "eagle-import:0603X90H")
      (fields (field (name "VOLTAGE") "25V") (field (name "MANUFACTURER") "MURATA"))
      (libsource (lib "eagle-import") (part "GRM188R61E104KA01"))
    )
    (comp (ref "C52")
      (value "0.1uF")
      (footprint "eagle-import:0603X90H")
      (fields (field (name "VOLTAGE") "25V") (field (name "MANUFACTURER") "MURATA"))
      (libsource (lib "eagle-import") (part "GRM188R61E104KA01"))
    )
    (comp (ref "C53")
      (value "0.1uF")
      (footprint "eagle-import:0603X90H")
      (fields (field (name "VOLTAGE") "25V") (field (name "MANUFACTURER") "MURATA"))
      (libsource (lib "eagle-import") (part "GRM188R61E104KA01"))
    )
    (comp (ref "J11")
      (value "CON_1X10_2211-10-S-02")
      (footprint "eagle-import:CONF1X10-254P_2612X240X850H_TH")
      (fields (field (name "MANUFACTURER") "SINGATRON"))
      (libsource (lib "eagle-import") (part "CON_1X10_2211-10-S-02"))
    )
    (comp (ref "J12")
      (value "CON_2X3_2202-06-S-02-6.0")
      (footprint "eagle-import:CONM2X3-254P_762X500X860H_TH")
      (fields (field (name "MANUFACTURER") "SINGATRON"))
      (libsource (lib "eagle-import") (part "CON_2X3_2202-06-S-02-6.0"))
    )
    (comp (ref "J13")
      (value "CON_1X8_2211-08-S-02-3.2_IO")
      (footprint "eagle-import:CONF1X8-254P_2104X240X850H_TH")
      (fields (field (name "MANUFACTURER") "SINGATRON"))
      (libsource (lib "eagle-import") (part "CON_1X8_2211-08-S-02-3.2_IO"))
    )
    (comp (ref "J14")
      (value "CON_1X6_2211-06-S-02-3.2")
      (footprint "eagle-import:CONF1X6-254P_1596X240X850H_TH")
      (fields (field (name "MANUFACTURER") "SINGATRON"))
      (libsource (lib "eagle-import") (part "CON_1X6_2211-06-S-02-3.2"))
    )
    (comp (ref "R27")
      (value "200K ohm")
      (footprint "eagle-import:0603X90H")
      (fields
        (field (name "TOL") "5%")
        (field (name "SIZE") "0603")
        (field (name "MANUFACTURER") "VISHAY-DALE")
      )
      (libsource (lib "eagle-import") (part "CRCW0603200KJNEB"))
    )
    (comp (ref "R28")
      (value "200K ohm")
      (footprint "eagle-import:0603X90H")
      (fields
        (field (name "TOL") "5%")
        (field (name "SIZE") "0603")
        (field (name "MANUFACTURER") "VISHAY-DALE")
      )
      (libsource (lib "eagle-import") (part "CRCW0603200KJNEB"))
    )
    (comp (ref "R29")
      (value "200K ohm")
      (footprint "eagle-import:0603X90H")
      (fields
        (field (name "TOL") "5%")
        (field (name "SIZE") "0603")
        (field (name "MANUFACTURER") "VISHAY-DALE")
      )
      (libsource (lib "eagle-import") (part "CRCW0603200KJNEB"))
    )
    (comp (ref "R33")
      (value "10K ohm")
      (footprint "eagle-import:0603X90H")
      (fields
        (field (name "TOL") "1%")
        (field (name "SIZE") "0603")
        (field (name "MANUFACTURER") "VISHAY-DALE")
      )
      (libsource (lib "eagle-import") (part "CRCW060310K0FKEA"))
    )
    (comp (ref "R34")
      (value "1.8K ohm")
      (footprint "eagle-import:0603X90H")
      (fields
        (field (name "TOL") "1%")
        (field (name "SIZE") "0603")
        (field (name "MANUFACTURER") "VISHAY-DALE")
      )
      (libsource (lib "eagle-import") (part "CRCW06031K80FKEBC"))
    )
    (comp (ref "R62")
      (value "10K ohm")
      (footprint "eagle-import:0603X90H")
      (fields (field (name "MANUFACTURER") "VISHAY-DALE"))
      (libsource (lib "eagle-import") (part "CRCW060310K0FKEA"))
    )
    (comp (ref "U11")
      (value "IC_LSF0108PWR")
      (footprint "eagle-import:SOIC20-65P_440X650X120H")
      (fields (field (name "MANUFACTURER") "TEXAS INSTRUMENTS"))
      (libsource (lib "eagle-import") (part "IC_LSF0108PWR"))
    )
    (comp (ref "U14")
      (value "IC_LSF0108PWR")
      (footprint "eagle-import:SOIC20-65P_440X650X120H")
      (fields (field (name "MANUFACTURER") "TEXAS INSTRUMENTS"))
      (libsource (lib "eagle-import") (part "IC_LSF0108PWR"))
    )
    (comp (ref "U15")
      (value "IC_LSF0108PWR")
      (footprint "eagle-import:SOIC20-65P_440X650X120H")
      (fields (field (name "MANUFACTURER") "TEXAS INSTRUMENTS"))
      (libsource (lib "eagle-import") (part "IC_LSF0108PWR"))
    )
    (comp (ref "U201")
      (value "IC_MX25V1635FM2I_FLASH")
      (footprint "eagle-import:SOIC8-127P_528X528X216H_1PRIMARY")
      (fields (field (name "MANUFACTURER") "MACRONIX"))
      (libsource (lib "eagle-import") (part "IC_MX25V1635FM2I_FLASH"))
    )
    (comp (ref "C1")
      (value "1.2pF")
      (footprint "eagle-import:0603X90H")
      (fields
        (field (name "VOLTAGE") "50V")
        (field (name "TOL") "0.25pF")
        (field (name "COEF") "C0G")
        (field (name "SIZE") "0603")
        (field (name "MANUFACTURER") "YAGEO")
      )
      (libsource (lib "eagle-import") (part "CC0603CRNPO9BN1R2"))
    )
    (comp (ref "C2")
      (value "0.1uF")
      (footprint "eagle-import:0603X90H")
      (fields (field (name "VOLTAGE") "25V") (field (name "MANUFACTURER") "MURATA"))
      (libsource (lib "eagle-import") (part "GRM188R61E104KA01_NOSTUFF"))
    )
    (comp (ref "C3")
      (value "10pF")
      (footprint "eagle-import:0603X90H")
      (fields
        (field (name "VOLTAGE") "50V")
        (field (name "TOL") "5%")
        (field (name "COEF") "C0G")
        (field (name "SIZE") "0603")
        (field (name "MANUFACTURER") "MURATA")
      )
      (libsource (lib "eagle-import") (part "GRM1885C1H100JA01F"))
    )
    (comp (ref "C17")
      (value "4.7uF")
      (footprint "eagle-import:0603X90H")
      (fields (field (name "VOLTAGE") "35V") (field (name "MANUFACTURER") "MURATA"))
      (libsource (lib "eagle-import") (part "GRM188R6YA475KE15D"))
    )
    (comp (ref "C20")
      (value "10uF")
      (footprint "eagle-import:0603X90H")
      (fields (field (name "VOLTAGE") "25V") (field (name "MANUFACTURER") "MURATA"))
      (libsource (lib "eagle-import") (part "GRM188R61E106MA73D"))
    )
    (comp (ref "C21")
      (value "4.7uF")
      (footprint "eagle-import:0603X90H")
      (fields (field (name "VOLTAGE") "16V") (field (name "MANUFACTURER") "MURATA"))
      (libsource (lib "eagle-import") (part "GRM188R61C475KAAJD"))
    )
    (comp (ref "C22")
      (value "0.1uF")
      (footprint "eagle-import:0603X90H")
      (fields (field (name "VOLTAGE") "25V") (field (name "MANUFACTURER") "MURATA"))
      (libsource (lib "eagle-import") (part "GRM188R61E104KA01"))
    )
    (comp (ref "C23")
      (value "10uF")
      (footprint "eagle-import:0603X90H")
      (fields (field (name "VOLTAGE") "25V") (field (name "MANUFACTURER") "MURATA"))
      (libsource (lib "eagle-import") (part "GRM188R61E106MA73D"))
    )
    (comp (ref "C24")
      (value "0.1uF")
      (footprint "eagle-import:0603X90H")
      (fields (field (name "VOLTAGE") "25V") (field (name "MANUFACTURER") "MURATA"))
      (libsource (lib "eagle-import") (part "GRM188R61E104KA01"))
    )
    (comp (ref "C25")
      (value "4.7uF")
      (footprint "eagle-import:0603X90H")
      (fields (field (name "VOLTAGE") "16V") (field (name "MANUFACTURER") "MURATA"))
      (libsource (lib "eagle-import") (part "GRM188R61C475KAAJD"))
    )
    (comp (ref "C26")
      (value "0.1uF")
      (footprint "eagle-import:0603X90H")
      (fields (field (name "VOLTAGE") "25V") (field (name "MANUFACTURER") "MURATA"))
      (libsource (lib "eagle-import") (part "GRM188R61E104KA01"))
    )
    (comp (ref "C28")
      (value "0.1uF")
      (footprint "eagle-import:0603X90H")
      (fields (field (name "VOLTAGE") "25V") (field (name "MANUFACTURER") "MURATA"))
      (libsource (lib "eagle-import") (part "GRM188R61E104KA01"))
    )
    (comp (ref "C29")
      (value "4.7uF")
      (footprint "eagle-import:0603X90H")
      (fields (field (name "VOLTAGE") "16V") (field (name "MANUFACTURER") "MURATA"))
      (libsource (lib "eagle-import") (part "GRM188R61C475KAAJD"))
    )
    (comp (ref "C30")
      (value "0.1uF")
      (footprint "eagle-import:0603X90H")
      (fields (field (name "VOLTAGE") "25V") (field (name "MANUFACTURER") "MURATA"))
      (libsource (lib "eagle-import") (part "GRM188R61E104KA01"))
    )
    (comp (ref "C31")
      (value "4.7uF")
      (footprint "eagle-import:0603X90H")
      (fields (field (name "VOLTAGE") "16V") (field (name "MANUFACTURER") "MURATA"))
      (libsource (lib "eagle-import") (part "GRM188R61C475KAAJD"))
    )
    (comp (ref "C32")
      (value "0.1uF")
      (footprint "eagle-import:0603X90H")
      (fields (field (name "VOLTAGE") "25V") (field (name "MANUFACTURER") "MURATA"))
      (libsource (lib "eagle-import") (part "GRM188R61E104KA01"))
    )
    (comp (ref "C33")
      (value "4.7uF")
      (footprint "eagle-import:0603X90H")
      (fields (field (name "VOLTAGE") "16V") (field (name "MANUFACTURER") "MURATA"))
      (libsource (lib "eagle-import") (part "GRM188R61C475KAAJD"))
    )
    (comp (ref "C35")
      (value "0.1uF")
      (footprint "eagle-import:0603X90H")
      (fields (field (name "VOLTAGE") "25V") (field (name "MANUFACTURER") "MURATA"))
      (libsource (lib "eagle-import") (part "GRM188R61E104KA01"))
    )
    (comp (ref "C38")
      (value "0.1uF")
      (footprint "eagle-import:0603X90H")
      (fields (field (name "VOLTAGE") "25V") (field (name "MANUFACTURER") "MURATA"))
      (libsource (lib "eagle-import") (part "GRM188R61E104KA01_NOSTUFF"))
    )
    (comp (ref "C45")
      (value "0.1uF")
      (footprint "eagle-import:0603X90H")
      (fields (field (name "VOLTAGE") "25V") (field (name "MANUFACTURER") "MURATA"))
      (libsource (lib "eagle-import") (part "GRM188R61E104KA01"))
    )
    (comp (ref "C46")
      (value "0.1uF")
      (footprint "eagle-import:0603X90H")
      (fields (field (name "VOLTAGE") "25V") (field (name "MANUFACTURER") "MURATA"))
      (libsource (lib "eagle-import") (part "GRM188R61E104KA01_NOSTUFF"))
    )
    (comp (ref "C47")
      (value "0.1uF")
      (footprint "eagle-import:0603X90H")
      (fields (field (name "VOLTAGE") "25V") (field (name "MANUFACTURER") "MURATA"))
      (libsource (lib "eagle-import") (part "GRM188R61E104KA01_NOSTUFF"))
    )
    (comp (ref "C48")
      (value "0.1uF")
      (footprint "eagle-import:0603X90H")
      (fields (field (name "VOLTAGE") "25V") (field (name "MANUFACTURER") "MURATA"))
      (libsource (lib "eagle-import") (part "GRM188R61E104KA01"))
    )
    (comp (ref "J18")
      (value "20449-001E-01")
      (footprint "eagle-import:CONN_COAX_MHF4")
      (fields (field (name "MANUFACTURER") "TAOGLAS LIMITED"))
      (libsource (lib "eagle-import") (part "20449-001E-01"))
    )
    (comp (ref "L1")
      (value "4.7nH")
      (footprint "eagle-import:0603X90H")
      (fields (field (name "MANUFACTURER") "MURATA"))
      (libsource (lib "eagle-import") (part "IND_LQG18HN4N7S00D"))
    )
    (comp (ref "L12")
      (value "22uH")
      (footprint "eagle-import:COIL_300X300X120H_NRH3012")
      (fields
        (field (name "PN") "NRH3012T220MN")
        (field (name "TOL") "20%")
        (field (name "MANUFACTURER") "TAIYO YUDEN")
      )
      (libsource (lib "eagle-import") (part "NRH3012T220MN"))
    )
    (comp (ref "R18")
      (value "0 ohm")
      (footprint "eagle-import:0603X90H")
      (fields (field (name "MANUFACTURER") "VISHAY-DALE"))
      (libsource (lib "eagle-import") (part "CRCW06030000Z0EA_NOSTUFF"))
    )
    (comp (ref "R19")
      (value "0 ohm")
      (footprint "eagle-import:0603X90H")
      (fields
        (field (name "TOL") "5%")
        (field (name "SIZE") "0603")
        (field (name "MANUFACTURER") "VISHAY-DALE")
      )
      (libsource (lib "eagle-import") (part "CRCW06030000Z0EA"))
    )
    (comp (ref "R24")
      (value "0 ohm")
      (footprint "eagle-import:0603X90H")
      (fields (field (name "MANUFACTURER") "VISHAY-DALE"))
      (libsource (lib "eagle-import") (part "CRCW06030000Z0EA_NOSTUFF"))
    )
    (comp (ref "R30")
      (value "10K ohm")
      (footprint "eagle-import:0603X90H")
      (fields (field (name "MANUFACTURER") "VISHAY-DALE"))
      (libsource (lib "eagle-import") (part "CRCW060310K0FKEA"))
    )
    (comp (ref "R35")
      (value "22 ohm")
      (footprint "eagle-import:0603X90H")
      (fields
        (field (name "TOL") "1%")
        (field (name "SIZE") "0603")
        (field (name "MANUFACTURER") "VISHAY-DALE")
      )
      (libsource (lib "eagle-import") (part "CRCW060322R0FKEA"))
    )
    (comp (ref "R59")
      (value "0 ohm")
      (footprint "eagle-import:0603X90H")
      (fields
        (field (name "TOL") "5%")
        (field (name "SIZE") "0603")
        (field (name "MANUFACTURER") "VISHAY-DALE")
      )
      (libsource (lib "eagle-import") (part "CRCW06030000Z0EA"))
    )
    (comp (ref "R86")
      (value "10M ohm")
      (footprint "eagle-import:SMR0402")
      (fields (field (name "MANUFACTURER") "KOA SPEER"))
      (libsource (lib "eagle-import") (part "RK73B1ETTP106J"))
    )
    (comp (ref "R88")
      (value "280 ohm")
      (footprint "eagle-import:SMR0402")
      (fields (field (name "MANUFACTURER") "KOA SPEER"))
      (libsource (lib "eagle-import") (part "RK73H1ETTP2800F"))
    )
    (comp (ref "U12")
      (value "CURIE")
      (footprint "eagle-import:BGA111_14X24-57P_805X1100X150H")
      (libsource (lib "eagle-import") (part "CURIE"))
    )
  )
  (nets
    (net (code "1") (name "AD0") (class "Default")
      (node (ref "J14") (pin "1") (pinfunction "P$1_1") (pintype "bidirectional"))
      (node (ref "U15") (pin "11") (pinfunction "B8_11") (pintype "bidirectional"))
    )
    (net (code "2") (name "AD1") (class "Default")
      (node (ref "J14") (pin "2") (pinfunction "P$2_2") (pintype "bidirectional"))
      (node (ref "U15") (pin "12") (pinfunction "B7_12") (pintype "bidirectional"))
    )
    (net (code "3") (name "AD2") (class "Default")
      (node (ref "J14") (pin "3") (pinfunction "P$3_3") (pintype "bidirectional"))
      (node (ref "U15") (pin "13") (pinfunction "B6_13") (pintype "bidirectional"))
    )
    (net (code "4") (name "AD3") (class "Default")
      (node (ref "J14") (pin "4") (pinfunction "P$4_4") (pintype "bidirectional"))
      (node (ref "U15") (pin "14") (pinfunction "B5_14") (pintype "bidirectional"))
    )
    (net (code "5") (name "AD4_SDA") (class "Default")
      (node (ref "J11") (pin "9") (pinfunction "AD4/SDA_9") (pintype "bidirectional"))
      (node (ref "J14") (pin "5") (pinfunction "P$5_5") (pintype "bidirectional"))
      (node (ref "U15") (pin "15") (pinfunction "B4_15") (pintype "bidirectional"))
    )
    (net (code "6") (name "AD5_SCL") (class "Default")
      (node (ref "J11") (pin "10") (pinfunction "AD5/SCL_10") (pintype "bidirectional"))
      (node (ref "J14") (pin "6") (pinfunction "P$6_6") (pintype "bidirectional"))
      (node (ref "U15") (pin "16") (pinfunction "B3_16") (pintype "bidirectional"))
    )
    (net (code "7") (name "AD09{slash}SS1_3V_AD5") (class "Default")
      (node (ref "U12") (pin "K21") (pinfunction "UART1_RTS/AN09_K21") (pintype "bidirectional"))
      (node (ref "U12") (pin "N24") (pinfunction "I2C0_SS_SCL_N24") (pintype "bidirectional"))
      (node (ref "U15") (pin "5") (pinfunction "A3_5") (pintype "bidirectional"))
    )
    (net (code "8") (name "AD10{slash}SS2_3V_AD0") (class "Default")
      (node (ref "U12") (pin "J2") (pinfunction "GPIO/AIN_10_J2") (pintype "bidirectional"))
      (node (ref "U15") (pin "10") (pinfunction "A8_10") (pintype "bidirectional"))
    )
    (net (code "9") (name "AD11{slash}SS3_3V_AD1") (class "Default")
      (node (ref "U12") (pin "H21") (pinfunction "GPIO/AIN_11_H21") (pintype "bidirectional"))
      (node (ref "U15") (pin "9") (pinfunction "A7_9") (pintype "bidirectional"))
    )
    (net (code "10") (name "AD12{slash}SS4_3V_AD2") (class "Default")
      (node (ref "U12") (pin "H2") (pinfunction "GPIO/AIN_12_H2") (pintype "bidirectional"))
      (node (ref "U15") (pin "8") (pinfunction "A6_8") (pintype "bidirectional"))
    )
    (net (code "11") (name "AD13{slash}SS5_3V_AD3") (class "Default")
      (node (ref "U12") (pin "L2") (pinfunction "GPIO/AIN_13_L2") (pintype "bidirectional"))
      (node (ref "U15") (pin "7") (pinfunction "A5_7") (pintype "bidirectional"))
    )
    (net (code "12") (name "AD14{slash}SS6_3V_AD4") (class "Default")
      (node (ref "U12") (pin "C24") (pinfunction "GPIO/AIN_14_C24") (pintype "bidirectional"))
      (node (ref "U12") (pin "N23") (pinfunction "I2C0_SS_SDA_N23") (pintype "bidirectional"))
      (node (ref "U15") (pin "6") (pinfunction "A4_6") (pintype "bidirectional"))
    )
    (net (code "13") (name "AREF") (class "Default")
      (node (ref "J11") (pin "8") (pinfunction "AREF_8") (pintype "bidirectional"))
    )
    (net (code "14") (name "ATPCTS{slash}IO9_3V_IO14") (class "Default")
      (node (ref "U12") (pin "J22") (pinfunction "UART1_CTS_J22") (pintype "bidirectional"))
      (node (ref "U14") (pin "4") (pinfunction "A2_4") (pintype "bidirectional"))
    )
    (net (code "15") (name "ATPMISO{slash}IO1_3V_IO12") (class "Default")
      (node (ref "U12") (pin "B22") (pinfunction "SPI1_M_MISO_B22") (pintype "bidirectional"))
      (node (ref "U12") (pin "G3") (pinfunction "ATP_SPI_S_MISO_G3") (pintype "bidirectional"))
      (node (ref "U14") (pin "6") (pinfunction "A4_6") (pintype "bidirectional"))
    )
    (net (code "16") (name "ATPMOSI{slash}IO3_3V_IO11") (class "Default")
      (node (ref "U12") (pin "E22") (pinfunction "SPI1_M_MOSI_E22") (pintype "bidirectional"))
      (node (ref "U12") (pin "F4") (pinfunction "ATP_SPI_S_MOSI_F4") (pintype "bidirectional"))
      (node (ref "U14") (pin "7") (pinfunction "A5_7") (pintype "bidirectional"))
    )
    (net (code "17") (name "ATPSCK{slash}IO2_3V_IO13") (class "Default")
      (node (ref "R65") (pin "1") (pinfunction "1_1") (pintype "bidirectional"))
      (node (ref "U12") (pin "C21") (pinfunction "SPI1_M_SCK_C21") (pintype "bidirectional"))
      (node (ref "U12") (pin "E4") (pinfunction "ATP_SPI_S_SCK_E4") (pintype "bidirectional"))
      (node (ref "U14") (pin "5") (pinfunction "A3_5") (pintype "bidirectional"))
      (node (ref "U16") (pin "2") (pinfunction "A_2") (pintype "bidirectional"))
    )
    (net (code "18") (name "ATPSS{slash}IO0_3V_IO10") (class "Default")
      (node (ref "U12") (pin "D22") (pinfunction "SPI1_M_CS0_D22") (pintype "bidirectional"))
      (node (ref "U12") (pin "F3") (pinfunction "ATP_SPI_S_CS_F3") (pintype "bidirectional"))
      (node (ref "U14") (pin "8") (pinfunction "A6_8") (pintype "bidirectional"))
    )
    (net (code "19") (name "AVD_OPM_2P6") (class "Default")
      (node (ref "R88") (pin "1") (pinfunction "1_1") (pintype "bidirectional"))
      (node (ref "U12") (pin "J1") (pinfunction "AVD_OPM_2P6_J1") (pintype "bidirectional"))
    )
    (net (code "20") (name "BATT_ISET") (class "Default")
      (node (ref "R24") (pin "1") (pinfunction "1_1") (pintype "bidirectional"))
      (node (ref "U12") (pin "L22") (pinfunction "BATT_ISET_L22") (pintype "bidirectional"))
    )
    (net (code "21") (name "BT_ANT_50") (class "Default")
      (node (ref "C3") (pin "2") (pinfunction "2_2") (pintype "bidirectional"))
      (node (ref "C38") (pin "1") (pinfunction "1_1") (pintype "bidirectional"))
      (node (ref "C46") (pin "1") (pinfunction "1_1") (pintype "bidirectional"))
      (node (ref "R18") (pin "2") (pinfunction "2_2") (pintype "bidirectional"))
      (node (ref "R19") (pin "1") (pinfunction "1_1") (pintype "bidirectional"))
    )
    (net (code "22") (name "BT_ANT_50_R") (class "Default")
      (node (ref "C1") (pin "1") (pinfunction "1_1") (pintype "bidirectional"))
      (node (ref "L1") (pin "1") (pinfunction "1_1") (pintype "bidirectional"))
      (node (ref "R19") (pin "2") (pinfunction "2_2") (pintype "bidirectional"))
    )
    (net (code "23") (name "BT_ANT_EXT") (class "Default")
      (node (ref "J18") (pin "1") (pinfunction "1_1") (pintype "bidirectional"))
      (node (ref "R18") (pin "1") (pinfunction "1_1") (pintype "bidirectional"))
    )
    (net (code "24") (name "BT_ANT_INT") (class "Default")
      (node (ref "C1") (pin "2") (pinfunction "2_2") (pintype "bidirectional"))
      (node (ref "C2") (pin "1") (pinfunction "1_1") (pintype "bidirectional"))
    )
    (net (code "25") (name "BT_AOUT_50") (class "Default")
      (node (ref "C3") (pin "1") (pinfunction "1_1") (pintype "bidirectional"))
      (node (ref "C47") (pin "1") (pinfunction "1_1") (pintype "bidirectional"))
      (node (ref "U12") (pin "F24") (pinfunction "BLE_RF_F24") (pintype "bidirectional"))
    )
    (net (code "26") (name "BUCK_VOUT") (class "Default")
      (node (ref "C35") (pin "1") (pinfunction "1_1") (pintype "bidirectional"))
      (node (ref "U12") (pin "K1") (pinfunction "BUCK_VOUT_K1") (pintype "bidirectional"))
    )
    (net (code "27") (name "CURIE_VBUS") (class "Default")
      (node (ref "R12") (pin "2") (pinfunction "2_2") (pintype "bidirectional"))
      (node (ref "R59") (pin "2") (pinfunction "2_2") (pintype "bidirectional"))
    )
    (net (code "28") (name "D13") (class "Default")
      (node (ref "D13") (pin "1") (pinfunction "A_1") (pintype "bidirectional"))
      (node (ref "R14") (pin "2") (pinfunction "2_2") (pintype "bidirectional"))
    )
    (net (code "29") (name "D13_R") (class "Default")
      (node (ref "R14") (pin "1") (pinfunction "1_1") (pintype "bidirectional"))
      (node (ref "U16") (pin "4") (pinfunction "Y_4") (pintype "bidirectional"))
    )
    (net (code "30") (name "DBG_AP_JTAG_TCK") (class "Default")
      (node (ref "J15") (pin "4") (pinfunction "P$4_4") (pintype "bidirectional"))
      (node (ref "TPB13") (pin "1") (pinfunction "1_1") (pintype "bidirectional"))
      (node (ref "U12") (pin "L23") (pinfunction "ATP_TCK_L23") (pintype "bidirectional"))
    )
    (net (code "31") (name "DBG_AP_JTAG_TDI") (class "Default")
      (node (ref "J15") (pin "8") (pinfunction "P$8_8") (pintype "bidirectional"))
      (node (ref "TPB15") (pin "1") (pinfunction "1_1") (pintype "bidirectional"))
      (node (ref "U12") (pin "M21") (pinfunction "ATP_TDI_M21") (pintype "bidirectional"))
    )
    (net (code "32") (name "DBG_AP_JTAG_TDO") (class "Default")
      (node (ref "J15") (pin "6") (pinfunction "P$6_6") (pintype "bidirectional"))
      (node (ref "TPB14") (pin "1") (pinfunction "1_1") (pintype "bidirectional"))
      (node (ref "U12") (pin "M23") (pinfunction "ATP_TDO_M23") (pintype "bidirectional"))
    )
    (net (code "33") (name "DBG_AP_JTAG_TMS") (class "Default")
      (node (ref "J15") (pin "2") (pinfunction "P$2_2") (pintype "bidirectional"))
      (node (ref "TPB12") (pin "1") (pinfunction "1_1") (pintype "bidirectional"))
      (node (ref "U12") (pin "L24") (pinfunction "ATP_TMS_L24") (pintype "bidirectional"))
    )
    (net (code "34") (name "DBG_AP_JTAG_TRST_N") (class "Default")
      (node (ref "J15") (pin "10") (pinfunction "P$10_10") (pintype "bidirectional"))
      (node (ref "TPB16") (pin "1") (pinfunction "1_1") (pintype "bidirectional"))
      (node (ref "U12") (pin "K23") (pinfunction "ATP_TRST_B_K23") (pintype "bidirectional"))
    )
    (net (code "35") (name "DC_IN_5V_20V") (class "Default")
      (node (ref "C36") (pin "1") (pinfunction "1_1") (pintype "bidirectional"))
      (node (ref "C50") (pin "1") (pinfunction "1_1") (pintype "bidirectional"))
      (node (ref "D17") (pin "1") (pinfunction "1_1") (pintype "bidirectional"))
      (node (ref "FB1") (pin "1") (pinfunction "1_1") (pintype "bidirectional"))
      (node (ref "J10") (pin "8") (pinfunction "P$8_8") (pintype "bidirectional"))
      (node (ref "R81") (pin "1") (pinfunction "1_1") (pintype "bidirectional"))
      (node (ref "R83") (pin "1") (pinfunction "1_1") (pintype "bidirectional"))
    )
    (net (code "36") (name "DC_IN_5V_20V_FIL") (class "Default")
      (node (ref "D18") (pin "2") (pinfunction "2_2") (pintype "bidirectional"))
      (node (ref "FB1") (pin "2") (pinfunction "2_2") (pintype "bidirectional"))
    )
    (net (code "37") (name "DC_IN_JACK") (class "Default")
      (node (ref "D17") (pin "2") (pinfunction "2_2") (pintype "bidirectional"))
      (node (ref "J16") (pin "1") (pinfunction "1_1") (pintype "passive"))
      (node (ref "TPB20") (pin "1") (pinfunction "1_1") (pintype "bidirectional"))
    )
    (net (code "38") (name "EN_V3P3") (class "Default")
      (node (ref "R89") (pin "2") (pinfunction "2_2") (pintype "bidirectional"))
      (node (ref "U205") (pin "3") (pinfunction "EN_3") (pintype "bidirectional"))
    )
    (net (code "39") (name "ESR3_LX") (class "Default")
      (node (ref "L12") (pin "1") (pinfunction "1_1") (pintype "bidirectional"))
      (node (ref "U12") (pin "P4") (pinfunction "ESR3_LX_P4") (pintype "bidirectional"))
    )
    (net (code "40") (name "GND") (class "Default")
      (node (ref "C11") (pin "2") (pinfunction "2_2") (pintype "bidirectional"))
      (node (ref "C12") (pin "2") (pinfunction "2_2") (pintype "bidirectional"))
      (node (ref "C13") (pin "2") (pinfunction "2_2") (pintype "bidirectional"))
      (node (ref "C14") (pin "2") (pinfunction "2_2") (pintype "bidirectional"))
      (node (ref "C15") (pin "2") (pinfunction "2_2") (pintype "bidirectional"))
      (node (ref "C16") (pin "2") (pinfunction "2_2") (pintype "bidirectional"))
      (node (ref "C17") (pin "2") (pinfunction "2_2") (pintype "bidirectional"))
      (node (ref "C18") (pin "2") (pinfunction "2_2") (pintype "bidirectional"))
      (node (ref "C19") (pin "2") (pinfunction "2_2") (pintype "bidirectional"))
      (node (ref "C2") (pin "2") (pinfunction "2_2") (pintype "bidirectional"))
      (node (ref "C20") (pin "2") (pinfunction "2_2") (pintype "bidirectional"))
      (node (ref "C21") (pin "2") (pinfunction "2_2") (pintype "bidirectional"))
      (node (ref "C22") (pin "2") (pinfunction "2_2") (pintype "bidirectional"))
      (node (ref "C23") (pin "2") (pinfunction "2_2") (pintype "bidirectional"))
      (node (ref "C24") (pin "2") (pinfunction "2_2") (pintype "bidirectional"))
      (node (ref "C25") (pin "2") (pinfunction "2_2") (pintype "bidirectional"))
      (node (ref "C26") (pin "2") (pinfunction "2_2") (pintype "bidirectional"))
      (node (ref "C28") (pin "2") (pinfunction "2_2") (pintype "bidirectional"))
      (node (ref "C29") (pin "2") (pinfunction "2_2") (pintype "bidirectional"))
      (node (ref "C30") (pin "2") (pinfunction "2_2") (pintype "bidirectional"))
      (node (ref "C31") (pin "2") (pinfunction "2_2") (pintype "bidirectional"))
      (node (ref "C32") (pin "2") (pinfunction "2_2") (pintype "bidirectional"))
      (node (ref "C33") (pin "2") (pinfunction "2_2") (pintype "bidirectional"))
      (node (ref "C35") (pin "2") (pinfunction "2_2") (pintype "bidirectional"))
      (node (ref "C36") (pin "2") (pinfunction "2_2") (pintype "bidirectional"))
      (node (ref "C38") (pin "2") (pinfunction "2_2") (pintype "bidirectional"))
      (node (ref "C39") (pin "2") (pinfunction "2_2") (pintype "bidirectional"))
      (node (ref "C41") (pin "2") (pinfunction "2_2") (pintype "bidirectional"))
      (node (ref "C42") (pin "2") (pinfunction "2_2") (pintype "bidirectional"))
      (node (ref "C43") (pin "2") (pinfunction "2_2") (pintype "bidirectional"))
      (node (ref "C44") (pin "2") (pinfunction "2_2") (pintype "bidirectional"))
      (node (ref "C45") (pin "2") (pinfunction "2_2") (pintype "bidirectional"))
      (node (ref "C46") (pin "2") (pinfunction "2_2") (pintype "bidirectional"))
      (node (ref "C47") (pin "2") (pinfunction "2_2") (pintype "bidirectional"))
      (node (ref "C48") (pin "2") (pinfunction "2_2") (pintype "bidirectional"))
      (node (ref "C49") (pin "2") (pinfunction "2_2") (pintype "bidirectional"))
      (node (ref "C50") (pin "2") (pinfunction "2_2") (pintype "bidirectional"))
      (node (ref "C51") (pin "2") (pinfunction "2_2") (pintype "bidirectional"))
      (node (ref "C52") (pin "2") (pinfunction "2_2") (pintype "bidirectional"))
      (node (ref "C53") (pin "2") (pinfunction "2_2") (pintype "bidirectional"))
      (node (ref "C54") (pin "2") (pinfunction "2_2") (pintype "bidirectional"))
      (node (ref "C55") (pin "2") (pinfunction "2_2") (pintype "bidirectional"))
      (node (ref "C56") (pin "2") (pinfunction "2_2") (pintype "bidirectional"))
      (node (ref "C57") (pin "2") (pinfunction "2_2") (pintype "bidirectional"))
      (node (ref "C58") (pin "2") (pinfunction "2_2") (pintype "bidirectional"))
      (node (ref "D10") (pin "2") (pinfunction "K_2") (pintype "bidirectional"))
      (node (ref "D13") (pin "2") (pinfunction "K_2") (pintype "bidirectional"))
      (node (ref "ESD10") (pin "2") (pinfunction "2_2") (pintype "bidirectional"))
      (node (ref "ESD11") (pin "2") (pinfunction "2_2") (pintype "bidirectional"))
      (node (ref "J10") (pin "6") (pinfunction "P$6_6") (pintype "bidirectional"))
      (node (ref "J10") (pin "7") (pinfunction "P$7_7") (pintype "bidirectional"))
      (node (ref "J11") (pin "7") (pinfunction "GND_7") (pintype "bidirectional"))
      (node (ref "J12") (pin "6") (pinfunction "P$6_6") (pintype "bidirectional"))
      (node (ref "J15") (pin "3") (pinfunction "P$3_3") (pintype "bidirectional"))
      (node (ref "J15") (pin "5") (pinfunction "P$5_5") (pintype "bidirectional"))
      (node (ref "J15") (pin "9") (pinfunction "P$9_9") (pintype "bidirectional"))
      (node (ref "J16") (pin "2") (pinfunction "2_2") (pintype "passive"))
      (node (ref "J16") (pin "3") (pinfunction "3_3") (pintype "passive"))
      (node (ref "J17") (pin "4") (pinfunction "P$4_4") (pintype "bidirectional"))
      (node (ref "J17") (pin "5") (pinfunction "P$5_5") (pintype "bidirectional"))
      (node (ref "J17") (pin "6") (pinfunction "P$6_6") (pintype "bidirectional"))
      (node (ref "J18") (pin "2") (pinfunction "2_2") (pintype "bidirectional"))
      (node (ref "J18") (pin "3") (pinfunction "3_3") (pintype "bidirectional"))
      (node (ref "J18") (pin "4") (pinfunction "4_4") (pintype "bidirectional"))
      (node (ref "L1") (pin "2") (pinfunction "2_2") (pintype "bidirectional"))
      (node (ref "R24") (pin "2") (pinfunction "2_2") (pintype "bidirectional"))
      (node (ref "R57") (pin "2") (pinfunction "2_2") (pintype "bidirectional"))
      (node (ref "R62") (pin "2") (pinfunction "2_2") (pintype "bidirectional"))
      (node (ref "R65") (pin "2") (pinfunction "2_2") (pintype "bidirectional"))
      (node (ref "R71") (pin "2") (pinfunction "2_2") (pintype "bidirectional"))
      (node (ref "R73") (pin "2") (pinfunction "2_2") (pintype "bidirectional"))
      (node (ref "R75") (pin "2") (pinfunction "2_2") (pintype "bidirectional"))
      (node (ref "R77") (pin "2") (pinfunction "2_2") (pintype "bidirectional"))
      (node (ref "R82") (pin "2") (pinfunction "2_2") (pintype "bidirectional"))
      (node (ref "R84") (pin "2") (pinfunction "2_2") (pintype "bidirectional"))
      (node (ref "R86") (pin "2") (pinfunction "2_2") (pintype "bidirectional"))
      (node (ref "R91") (pin "2") (pinfunction "2_2") (pintype "bidirectional"))
      (node (ref "SH10") (pin "2") (pinfunction "2_2") (pintype "bidirectional"))
      (node (ref "SW10") (pin "1") (pinfunction "1_1") (pintype "bidirectional"))
      (node (ref "SW10") (pin "2") (pinfunction "2_2") (pintype "bidirectional"))
      (node (ref "SW12") (pin "3") (pinfunction "3_3") (pintype "bidirectional"))
      (node (ref "SW12") (pin "4") (pinfunction "4_4") (pintype "bidirectional"))
      (node (ref "TPB22") (pin "1") (pinfunction "1_1") (pintype "bidirectional"))
      (node (ref "TPB23") (pin "1") (pinfunction "1_1") (pintype "bidirectional"))
      (node (ref "U10") (pin "15") (pinfunction "PGND1_15") (pintype "bidirectional"))
      (node (ref "U10") (pin "16") (pinfunction "PGND2_16") (pintype "bidirectional"))
      (node (ref "U10") (pin "17") (pinfunction "THERM_17") (pintype "bidirectional"))
      (node (ref "U10") (pin "5") (pinfunction "FB_5") (pintype "bidirectional"))
      (node (ref "U10") (pin "6") (pinfunction "AGND_6") (pintype "bidirectional"))
      (node (ref "U10") (pin "7") (pinfunction "FSW_7") (pintype "bidirectional"))
      (node (ref "U11") (pin "1") (pinfunction "GND_1") (pintype "bidirectional"))
      (node (ref "U12") (pin "A2") (pinfunction "GND2_A2") (pintype "bidirectional"))
      (node (ref "U12") (pin "A24") (pinfunction "GND7_A24") (pintype "bidirectional"))
      (node (ref "U12") (pin "C23") (pinfunction "GND4_C23") (pintype "bidirectional"))
      (node (ref "U12") (pin "G21") (pinfunction "GND6_G21") (pintype "bidirectional"))
      (node (ref "U12") (pin "G24") (pinfunction "GND5_G24") (pintype "bidirectional"))
      (node (ref "U12") (pin "K24") (pinfunction "VIN_1_K24") (pintype "bidirectional"))
      (node (ref "U12") (pin "L21") (pinfunction "AGND_L21") (pintype "bidirectional"))
      (node (ref "U12") (pin "N21") (pinfunction "VIN_2_N21") (pintype "bidirectional"))
      (node (ref "U12") (pin "P1") (pinfunction "GND1_P1") (pintype "bidirectional"))
      (node (ref "U12") (pin "P22") (pinfunction "GND3_P22") (pintype "bidirectional"))
      (node (ref "U12") (pin "P24") (pinfunction "GND8_P24") (pintype "bidirectional"))
      (node (ref "U13") (pin "2") (pinfunction "GND1_2") (pintype "bidirectional"))
      (node (ref "U13") (pin "5") (pinfunction "GND2_5") (pintype "bidirectional"))
      (node (ref "U14") (pin "1") (pinfunction "GND_1") (pintype "bidirectional"))
      (node (ref "U15") (pin "1") (pinfunction "GND_1") (pintype "bidirectional"))
      (node (ref "U16") (pin "3") (pinfunction "GND_3") (pintype "bidirectional"))
      (node (ref "U201") (pin "4") (pinfunction "VSS_4") (pintype "bidirectional"))
      (node (ref "U202") (pin "2") (pinfunction "GND1_2") (pintype "bidirectional"))
      (node (ref "U202") (pin "3") (pinfunction "GND2_3") (pintype "bidirectional"))
      (node (ref "U203") (pin "4") (pinfunction "GND_4") (pintype "bidirectional"))
      (node (ref "U204") (pin "8") (pinfunction "GND_8") (pintype "bidirectional"))
      (node (ref "U205") (pin "1") (pinfunction "PGND_1") (pintype "bidirectional"))
      (node (ref "U205") (pin "4") (pinfunction "AGND_4") (pintype "bidirectional"))
      (node (ref "U205") (pin "5") (pinfunction "FB_5") (pintype "bidirectional"))
      (node (ref "U205") (pin "9") (pinfunction "THERM_9") (pintype "bidirectional"))
      (node (ref "U206") (pin "4") (pinfunction "GND_4") (pintype "bidirectional"))
    )
    (net (code "41") (name "I2S_TSCK{slash}IO18_3V_IO2") (class "Default")
      (node (ref "U11") (pin "8") (pinfunction "A6_8") (pintype "bidirectional"))
      (node (ref "U12") (pin "C2") (pinfunction "I2S_TSCK_C2") (pintype "bidirectional"))
    )
    (net (code "42") (name "I2S_TWS{slash}IO19_3V_IO4") (class "Default")
      (node (ref "U11") (pin "6") (pinfunction "A4_6") (pintype "bidirectional"))
      (node (ref "U12") (pin "C1") (pinfunction "I2S_TWS_C1") (pintype "bidirectional"))
    )
    (net (code "43") (name "I2S_TXD{slash}IO20_3V_IO7") (class "Default")
      (node (ref "U11") (pin "3") (pinfunction "A1_3") (pintype "bidirectional"))
      (node (ref "U12") (pin "D1") (pinfunction "I2S_TXD_D1") (pintype "bidirectional"))
    )
    (net (code "44") (name "IO0{slash}RXD") (class "Default")
      (node (ref "J13") (pin "1") (pinfunction "P$1_1") (pintype "bidirectional"))
      (node (ref "U11") (pin "11") (pinfunction "B8_11") (pintype "bidirectional"))
    )
    (net (code "45") (name "IO1{slash}TXD") (class "Default")
      (node (ref "J13") (pin "2") (pinfunction "P$2_2") (pintype "bidirectional"))
      (node (ref "U11") (pin "12") (pinfunction "B7_12") (pintype "bidirectional"))
    )
    (net (code "46") (name "IO2") (class "Default")
      (node (ref "J13") (pin "3") (pinfunction "P$3_3") (pintype "bidirectional"))
      (node (ref "U11") (pin "13") (pinfunction "B6_13") (pintype "bidirectional"))
    )
    (net (code "47") (name "IO3{slash}PWM0") (class "Default")
      (node (ref "J13") (pin "4") (pinfunction "P$4_4") (pintype "bidirectional"))
      (node (ref "U11") (pin "14") (pinfunction "B5_14") (pintype "bidirectional"))
    )
    (net (code "48") (name "IO4") (class "Default")
      (node (ref "J13") (pin "5") (pinfunction "P$5_5") (pintype "bidirectional"))
      (node (ref "U11") (pin "15") (pinfunction "B4_15") (pintype "bidirectional"))
    )
    (net (code "49") (name "IO5{slash}PWM1") (class "Default")
      (node (ref "J13") (pin "6") (pinfunction "P$6_6") (pintype "bidirectional"))
      (node (ref "U11") (pin "16") (pinfunction "B3_16") (pintype "bidirectional"))
    )
    (net (code "50") (name "IO6{slash}PWM2") (class "Default")
      (node (ref "J13") (pin "7") (pinfunction "P$7_7") (pintype "bidirectional"))
      (node (ref "U11") (pin "17") (pinfunction "B2_17") (pintype "bidirectional"))
    )
    (net (code "51") (name "IO7") (class "Default")
      (node (ref "J13") (pin "8") (pinfunction "P$8_8") (pintype "bidirectional"))
      (node (ref "U11") (pin "18") (pinfunction "B1_18") (pintype "bidirectional"))
    )
    (net (code "52") (name "IO8") (class "Default")
      (node (ref "J11") (pin "1") (pinfunction "IO8_1") (pintype "bidirectional"))
      (node (ref "U14") (pin "11") (pinfunction "B8_11") (pintype "bidirectional"))
    )
    (net (code "53") (name "IO9{slash}PWM3") (class "Default")
      (node (ref "J11") (pin "2") (pinfunction "IO9/PWM_2") (pintype "bidirectional"))
      (node (ref "U14") (pin "12") (pinfunction "B7_12") (pintype "bidirectional"))
    )
    (net (code "54") (name "IO10{slash}SS") (class "Default")
      (node (ref "J11") (pin "3") (pinfunction "SS/PWM_3") (pintype "bidirectional"))
      (node (ref "U14") (pin "13") (pinfunction "B6_13") (pintype "bidirectional"))
    )
    (net (code "55") (name "IO11{slash}MOSI") (class "Default")
      (node (ref "J11") (pin "4") (pinfunction "MOSI/PWM_4") (pintype "bidirectional"))
      (node (ref "J12") (pin "4") (pinfunction "P$4_4") (pintype "bidirectional"))
      (node (ref "U14") (pin "14") (pinfunction "B5_14") (pintype "bidirectional"))
    )
    (net (code "56") (name "IO12{slash}MISO") (class "Default")
      (node (ref "J11") (pin "5") (pinfunction "MISO_5") (pintype "bidirectional"))
      (node (ref "J12") (pin "1") (pinfunction "P$1_1") (pintype "bidirectional"))
      (node (ref "U14") (pin "15") (pinfunction "B4_15") (pintype "bidirectional"))
    )
    (net (code "57") (name "IO13{slash}SCK") (class "Default")
      (node (ref "J11") (pin "6") (pinfunction "SCK_6") (pintype "bidirectional"))
      (node (ref "J12") (pin "3") (pinfunction "P$3_3") (pintype "bidirectional"))
      (node (ref "U14") (pin "16") (pinfunction "B3_16") (pintype "bidirectional"))
    )
    (net (code "58") (name "IO14_NEW") (class "Default")
      (node (ref "J10") (pin "1") (pinfunction "P$1_1") (pintype "bidirectional"))
      (node (ref "U14") (pin "17") (pinfunction "B2_17") (pintype "bidirectional"))
    )
    (net (code "59") (name "LDO1P8_OUT") (class "Default")
      (node (ref "C48") (pin "1") (pinfunction "1_1") (pintype "bidirectional"))
      (node (ref "U12") (pin "L1") (pinfunction "LDO1P8_VOUT_L1") (pintype "bidirectional"))
    )
    (net (code "60") (name "MISO1{slash}IO9_3V_IO8") (class "Default")
      (node (ref "U12") (pin "B2") (pinfunction "I2S_RSCK_B2") (pintype "bidirectional"))
      (node (ref "U12") (pin "E3") (pinfunction "PLT_CLK_0_E3") (pintype "bidirectional"))
      (node (ref "U14") (pin "10") (pinfunction "A8_10") (pintype "bidirectional"))
    )
    (net (code "61") (name "M_RESET") (class "Default")
      (node (ref "R13") (pin "2") (pinfunction "2_2") (pintype "bidirectional"))
      (node (ref "U12") (pin "D23") (pinfunction "MRESET_B_D23") (pintype "bidirectional"))
    )
    (net (code "62") (name "M_RESET_R") (class "Default")
      (node (ref "C19") (pin "1") (pinfunction "1_1") (pintype "bidirectional"))
      (node (ref "R13") (pin "1") (pinfunction "1_1") (pintype "bidirectional"))
      (node (ref "SW10") (pin "3") (pinfunction "3_3") (pintype "bidirectional"))
      (node (ref "SW10") (pin "4") (pinfunction "4_4") (pintype "bidirectional"))
    )
    (net (code "63") (name "N$178") (class "Default")
      (node (ref "R30") (pin "2") (pinfunction "2_2") (pintype "bidirectional"))
      (node (ref "R86") (pin "1") (pinfunction "1_1") (pintype "bidirectional"))
      (node (ref "U12") (pin "B4") (pinfunction "ATP_RST_B_B4") (pintype "bidirectional"))
      (node (ref "U12") (pin "E23") (pinfunction "POR_B_E23") (pintype "bidirectional"))
      (node (ref "U204") (pin "4") (pinfunction "POR_B_4") (pintype "bidirectional"))
    )
    (net (code "64") (name "NOR_SWD_SCL") (class "Default")
      (node (ref "TPB11") (pin "1") (pinfunction "1_1") (pintype "bidirectional"))
      (node (ref "U12") (pin "D24") (pinfunction "BLE_SW_CLK_D24") (pintype "bidirectional"))
    )
    (net (code "65") (name "NOR_SWD_SDA") (class "Default")
      (node (ref "TPB10") (pin "1") (pinfunction "1_1") (pintype "bidirectional"))
      (node (ref "U12") (pin "E24") (pinfunction "BLE_SWDIO_E24") (pintype "bidirectional"))
    )
    (net (code "66") (name "Net-(U12A-VDD_PLAT_3P3)") (class "Default")
      (node (ref "C45") (pin "1") (pinfunction "1_1") (pintype "bidirectional"))
      (node (ref "U12") (pin "N2") (pinfunction "VDD_PLAT_3P3_N2") (pintype "bidirectional"))
    )
    (net (code "67") (name "Net-(U12C-VDD_USB)") (class "Default")
      (node (ref "C17") (pin "1") (pinfunction "1_1") (pintype "bidirectional"))
      (node (ref "R59") (pin "1") (pinfunction "1_1") (pintype "bidirectional"))
      (node (ref "U12") (pin "K4") (pinfunction "VDD_USB_K4") (pintype "bidirectional"))
    )
    (net (code "68") (name "OPM_2P6_DIS") (class "Default")
      (node (ref "R88") (pin "2") (pinfunction "2_2") (pintype "bidirectional"))
      (node (ref "U204") (pin "12") (pinfunction "OPM2P6_DIS_12") (pintype "bidirectional"))
    )
    (net (code "69") (name "PFET_ON") (class "Default")
      (node (ref "R84") (pin "1") (pinfunction "1_1") (pintype "bidirectional"))
      (node (ref "U203") (pin "1") (pinfunction "ON_1") (pintype "bidirectional"))
      (node (ref "U204") (pin "14") (pinfunction "PFET_ON_14") (pintype "bidirectional"))
    )
    (net (code "70") (name "PG_V3P3") (class "Default")
      (node (ref "R90") (pin "1") (pinfunction "1_1") (pintype "bidirectional"))
      (node (ref "U204") (pin "10") (pinfunction "PG_10") (pintype "bidirectional"))
      (node (ref "U205") (pin "8") (pinfunction "PG_8") (pintype "bidirectional"))
    )
    (net (code "71") (name "PV_BATT") (class "Default")
      (node (ref "C23") (pin "1") (pinfunction "1_1") (pintype "bidirectional"))
      (node (ref "C24") (pin "1") (pinfunction "1_1") (pintype "bidirectional"))
      (node (ref "U12") (pin "M1") (pinfunction "PV_BATT_M1") (pintype "bidirectional"))
    )
    (net (code "72") (name "PWM0{slash}SS10_3V_IO3") (class "Default")
      (node (ref "U11") (pin "7") (pinfunction "A5_7") (pintype "bidirectional"))
      (node (ref "U12") (pin "B1") (pinfunction "I2S_RWS_B1") (pintype "bidirectional"))
      (node (ref "U12") (pin "H1") (pinfunction "PWM0_OUT_H1") (pintype "bidirectional"))
    )
    (net (code "73") (name "PWM1{slash}SS11_3V_IO5") (class "Default")
      (node (ref "U11") (pin "5") (pinfunction "A3_5") (pintype "bidirectional"))
      (node (ref "U12") (pin "A3") (pinfunction "I2S_RXD_A3") (pintype "bidirectional"))
      (node (ref "U12") (pin "G2") (pinfunction "PWM1_OUT_G2") (pintype "bidirectional"))
    )
    (net (code "74") (name "PWM2{slash}SS12_3V_IO6") (class "Default")
      (node (ref "U11") (pin "4") (pinfunction "A2_4") (pintype "bidirectional"))
      (node (ref "U12") (pin "G1") (pinfunction "PWM2_OUT_G1") (pintype "bidirectional"))
    )
    (net (code "75") (name "PWM3{slash}SS13_3V_IO9") (class "Default")
      (node (ref "U12") (pin "F2") (pinfunction "PWM3_OUT_F2") (pintype "bidirectional"))
      (node (ref "U14") (pin "9") (pinfunction "A7_9") (pintype "bidirectional"))
    )
    (net (code "76") (name "PWRLED_R") (class "Default")
      (node (ref "D10") (pin "1") (pinfunction "A_1") (pintype "bidirectional"))
      (node (ref "R10") (pin "2") (pinfunction "2_2") (pintype "bidirectional"))
    )
    (net (code "77") (name "RST_SKETCH") (class "Default")
      (node (ref "J10") (pin "3") (pinfunction "P$3_3") (pintype "bidirectional"))
      (node (ref "J12") (pin "5") (pinfunction "P$5_5") (pintype "bidirectional"))
      (node (ref "R23") (pin "2") (pinfunction "2_2") (pintype "bidirectional"))
      (node (ref "U14") (pin "18") (pinfunction "B1_18") (pintype "bidirectional"))
    )
    (net (code "78") (name "RST_SKETCH_3V") (class "Default")
      (node (ref "U12") (pin "F22") (pinfunction "ATP_INT0_F22") (pintype "bidirectional"))
      (node (ref "U14") (pin "3") (pinfunction "A1_3") (pintype "bidirectional"))
    )
    (net (code "79") (name "RST_SKETCH_R") (class "Default")
      (node (ref "C41") (pin "1") (pinfunction "1_1") (pintype "bidirectional"))
      (node (ref "R23") (pin "1") (pinfunction "1_1") (pintype "bidirectional"))
      (node (ref "SW12") (pin "1") (pinfunction "1_1") (pintype "bidirectional"))
      (node (ref "SW12") (pin "2") (pinfunction "2_2") (pintype "bidirectional"))
    )
    (net (code "80") (name "RXD1{slash}SS9_3V_IO0") (class "Default")
      (node (ref "U11") (pin "10") (pinfunction "A8_10") (pintype "bidirectional"))
      (node (ref "U12") (pin "K22") (pinfunction "UART1_RX_K22") (pintype "bidirectional"))
    )
    (net (code "81") (name "RXLED") (class "Default")
      (node (ref "D15") (pin "2") (pinfunction "K_2") (pintype "bidirectional"))
      (node (ref "U12") (pin "C3") (pinfunction "SPI0_M_CS2_C3") (pintype "bidirectional"))
    )
    (net (code "82") (name "RXLED_R") (class "Default")
      (node (ref "D15") (pin "1") (pinfunction "A_1") (pintype "bidirectional"))
      (node (ref "R16") (pin "2") (pinfunction "2_2") (pintype "bidirectional"))
    )
    (net (code "83") (name "SP0_CLK_MEM") (class "Default")
      (node (ref "U12") (pin "C4") (pinfunction "SPI0_M_SCK_C4") (pintype "bidirectional"))
      (node (ref "U201") (pin "6") (pinfunction "SCK_6") (pintype "bidirectional"))
    )
    (net (code "84") (name "SP0_CS0_MEM") (class "Default")
      (node (ref "U12") (pin "B3") (pinfunction "SPI0_M_CS0_B3") (pintype "bidirectional"))
      (node (ref "U201") (pin "1") (pinfunction "CS_1") (pintype "bidirectional"))
    )
    (net (code "85") (name "SP0_MISO_MEM") (class "Default")
      (node (ref "U12") (pin "D4") (pinfunction "SPI0_M_MISO_D4") (pintype "bidirectional"))
      (node (ref "U201") (pin "2") (pinfunction "MISO_2") (pintype "bidirectional"))
    )
    (net (code "86") (name "SP0_MOSI_MEM") (class "Default")
      (node (ref "U12") (pin "D3") (pinfunction "SPI0_M_MOSI_D3") (pintype "bidirectional"))
      (node (ref "U201") (pin "5") (pinfunction "MOSI_5") (pintype "bidirectional"))
    )
    (net (code "87") (name "SP0_WP_MEM~{}") (class "Default")
      (node (ref "R62") (pin "1") (pinfunction "1_1") (pintype "bidirectional"))
      (node (ref "U12") (pin "A4") (pinfunction "SPI0_M_CS1_A4") (pintype "bidirectional"))
      (node (ref "U201") (pin "3") (pinfunction "WP_3") (pintype "bidirectional"))
    )
    (net (code "88") (name "TRIG_TRUE_D") (class "Default")
      (node (ref "C55") (pin "1") (pinfunction "1_1") (pintype "bidirectional"))
      (node (ref "R75") (pin "1") (pinfunction "1_1") (pintype "bidirectional"))
      (node (ref "R81") (pin "2") (pinfunction "2_2") (pintype "bidirectional"))
      (node (ref "U10") (pin "13") (pinfunction "ENA_13") (pintype "bidirectional"))
      (node (ref "U13") (pin "9") (pinfunction "ONB_9") (pintype "bidirectional"))
      (node (ref "U202") (pin "4") (pinfunction "DOUT_4") (pintype "bidirectional"))
    )
    (net (code "89") (name "TXD1{slash}SS8_3V_IO1") (class "Default")
      (node (ref "U11") (pin "9") (pinfunction "A7_9") (pintype "bidirectional"))
      (node (ref "U12") (pin "J21") (pinfunction "UART1_TX_J21") (pintype "bidirectional"))
    )
    (net (code "90") (name "TXLED") (class "Default")
      (node (ref "D14") (pin "2") (pinfunction "K_2") (pintype "bidirectional"))
      (node (ref "U12") (pin "D21") (pinfunction "SPI1_M_CS1_D21") (pintype "bidirectional"))
    )
    (net (code "91") (name "TXLED_R") (class "Default")
      (node (ref "D14") (pin "1") (pinfunction "A_1") (pintype "bidirectional"))
      (node (ref "R15") (pin "2") (pinfunction "2_2") (pintype "bidirectional"))
    )
    (net (code "92") (name "U10_DEF") (class "Default")
      (node (ref "R70") (pin "2") (pinfunction "2_2") (pintype "bidirectional"))
      (node (ref "R71") (pin "1") (pinfunction "1_1") (pintype "bidirectional"))
      (node (ref "U10") (pin "8") (pinfunction "DEF_8") (pintype "bidirectional"))
    )
    (net (code "93") (name "U10_SS") (class "Default")
      (node (ref "C15") (pin "1") (pinfunction "1_1") (pintype "bidirectional"))
      (node (ref "U10") (pin "9") (pinfunction "SS/TR_9") (pintype "bidirectional"))
    )
    (net (code "94") (name "U10_SW") (class "Default")
      (node (ref "L10") (pin "1") (pinfunction "1_1") (pintype "bidirectional"))
      (node (ref "U10") (pin "1") (pinfunction "SW1_1") (pintype "bidirectional"))
      (node (ref "U10") (pin "2") (pinfunction "SW2_2") (pintype "bidirectional"))
      (node (ref "U10") (pin "3") (pinfunction "SW3_3") (pintype "bidirectional"))
    )
    (net (code "95") (name "U10_VIN") (class "Default")
      (node (ref "C12") (pin "1") (pinfunction "1_1") (pintype "bidirectional"))
      (node (ref "C16") (pin "1") (pinfunction "1_1") (pintype "bidirectional"))
      (node (ref "D18") (pin "1") (pinfunction "1_1") (pintype "bidirectional"))
      (node (ref "R77") (pin "1") (pinfunction "1_1") (pintype "bidirectional"))
      (node (ref "U10") (pin "10") (pinfunction "AVIN_10") (pintype "bidirectional"))
      (node (ref "U10") (pin "11") (pinfunction "PVIN1_11") (pintype "bidirectional"))
      (node (ref "U10") (pin "12") (pinfunction "PVIN2_12") (pintype "bidirectional"))
    )
    (net (code "96") (name "U11_VREFB") (class "Default")
      (node (ref "C53") (pin "1") (pinfunction "1_1") (pintype "bidirectional"))
      (node (ref "R29") (pin "1") (pinfunction "1_1") (pintype "bidirectional"))
      (node (ref "U11") (pin "19") (pinfunction "VREF_B_19") (pintype "bidirectional"))
      (node (ref "U11") (pin "20") (pinfunction "EN_20") (pintype "bidirectional"))
    )
    (net (code "97") (name "U13_ISET") (class "Default")
      (node (ref "R74") (pin "1") (pinfunction "1_1") (pintype "bidirectional"))
      (node (ref "U13") (pin "8") (pinfunction "ISET_8") (pintype "bidirectional"))
    )
    (net (code "98") (name "U13_ISET_R") (class "Default")
      (node (ref "R73") (pin "1") (pinfunction "1_1") (pintype "bidirectional"))
      (node (ref "R74") (pin "2") (pinfunction "2_2") (pintype "bidirectional"))
      (node (ref "SH10") (pin "1") (pinfunction "1_1") (pintype "bidirectional"))
    )
    (net (code "99") (name "U14_VREFB") (class "Default")
      (node (ref "C52") (pin "1") (pinfunction "1_1") (pintype "bidirectional"))
      (node (ref "R28") (pin "1") (pinfunction "1_1") (pintype "bidirectional"))
      (node (ref "U14") (pin "19") (pinfunction "VREF_B_19") (pintype "bidirectional"))
      (node (ref "U14") (pin "20") (pinfunction "EN_20") (pintype "bidirectional"))
    )
    (net (code "100") (name "U15_VREFB") (class "Default")
      (node (ref "C51") (pin "1") (pinfunction "1_1") (pintype "bidirectional"))
      (node (ref "R27") (pin "1") (pinfunction "1_1") (pintype "bidirectional"))
      (node (ref "U15") (pin "19") (pinfunction "VREF_B_19") (pintype "bidirectional"))
      (node (ref "U15") (pin "20") (pinfunction "EN_20") (pintype "bidirectional"))
    )
    (net (code "101") (name "U202_VDD") (class "Default")
      (node (ref "C54") (pin "1") (pinfunction "1_1") (pintype "bidirectional"))
      (node (ref "R82") (pin "1") (pinfunction "1_1") (pintype "bidirectional"))
      (node (ref "R83") (pin "2") (pinfunction "2_2") (pintype "bidirectional"))
      (node (ref "U202") (pin "1") (pinfunction "VDD_1") (pintype "bidirectional"))
    )
    (net (code "102") (name "U205_SW") (class "Default")
      (node (ref "L14") (pin "1") (pinfunction "1_1") (pintype "bidirectional"))
      (node (ref "U205") (pin "7") (pinfunction "SW_7") (pintype "bidirectional"))
    )
    (net (code "103") (name "USBDN_CONN") (class "Default")
      (node (ref "R32") (pin "2") (pinfunction "2_2") (pintype "bidirectional"))
      (node (ref "TPB17") (pin "1") (pinfunction "1_1") (pintype "bidirectional"))
      (node (ref "U12") (pin "J23") (pinfunction "USB_DM_J23") (pintype "bidirectional"))
    )
    (net (code "104") (name "USBDP_CONN") (class "Default")
      (node (ref "R31") (pin "2") (pinfunction "2_2") (pintype "bidirectional"))
      (node (ref "TPB18") (pin "1") (pinfunction "1_1") (pintype "bidirectional"))
      (node (ref "U12") (pin "J24") (pinfunction "USB_DP_J24") (pintype "bidirectional"))
    )
    (net (code "105") (name "USBDP_CONN_R") (class "Default")
      (node (ref "ESD11") (pin "1") (pinfunction "1_1") (pintype "bidirectional"))
      (node (ref "J17") (pin "3") (pinfunction "P$3_3") (pintype "bidirectional"))
      (node (ref "R31") (pin "1") (pinfunction "1_1") (pintype "bidirectional"))
    )
    (net (code "106") (name "USB_5P00_PWR") (class "Default")
      (node (ref "C18") (pin "1") (pinfunction "1_1") (pintype "bidirectional"))
      (node (ref "C42") (pin "1") (pinfunction "1_1") (pintype "bidirectional"))
      (node (ref "J17") (pin "1") (pinfunction "P$1_1") (pintype "bidirectional"))
      (node (ref "R12") (pin "1") (pinfunction "1_1") (pintype "bidirectional"))
      (node (ref "TPB19") (pin "1") (pinfunction "1_1") (pintype "bidirectional"))
      (node (ref "U13") (pin "3") (pinfunction "VIN1_3") (pintype "bidirectional"))
      (node (ref "U13") (pin "6") (pinfunction "VIN2_6") (pintype "bidirectional"))
    )
    (net (code "107") (name "USDN_CONN_R") (class "Default")
      (node (ref "ESD10") (pin "1") (pinfunction "1_1") (pintype "bidirectional"))
      (node (ref "J17") (pin "2") (pinfunction "P$2_2") (pintype "bidirectional"))
      (node (ref "R32") (pin "1") (pinfunction "1_1") (pintype "bidirectional"))
    )
    (net (code "108") (name "V5_PFET_ON") (class "Default")
      (node (ref "R91") (pin "1") (pinfunction "1_1") (pintype "bidirectional"))
      (node (ref "R92") (pin "2") (pinfunction "2_2") (pintype "bidirectional"))
      (node (ref "U206") (pin "1") (pinfunction "ON_1") (pintype "bidirectional"))
    )
    (net (code "109") (name "VDD_PLAT_1P8") (class "Default")
      (node (ref "C28") (pin "1") (pinfunction "1_1") (pintype "bidirectional"))
      (node (ref "U12") (pin "M2") (pinfunction "VDD_PLAT_1P8_M2") (pintype "bidirectional"))
    )
    (net (code "110") (name "VDD_PLAT_3P3") (class "Default")
      (node (ref "C21") (pin "1") (pinfunction "1_1") (pintype "bidirectional"))
      (node (ref "C22") (pin "1") (pinfunction "1_1") (pintype "bidirectional"))
      (node (ref "C44") (pin "1") (pinfunction "1_1") (pintype "bidirectional"))
      (node (ref "J10") (pin "2") (pinfunction "P$2_2") (pintype "bidirectional"))
      (node (ref "J10") (pin "4") (pinfunction "P$4_4") (pintype "bidirectional"))
      (node (ref "J15") (pin "1") (pinfunction "P$1_1") (pintype "bidirectional"))
      (node (ref "R10") (pin "1") (pinfunction "1_1") (pintype "bidirectional"))
      (node (ref "R15") (pin "1") (pinfunction "1_1") (pintype "bidirectional"))
      (node (ref "R16") (pin "1") (pinfunction "1_1") (pintype "bidirectional"))
      (node (ref "R30") (pin "1") (pinfunction "1_1") (pintype "bidirectional"))
      (node (ref "R34") (pin "1") (pinfunction "1_1") (pintype "bidirectional"))
      (node (ref "R35") (pin "2") (pinfunction "2_2") (pintype "bidirectional"))
      (node (ref "R58") (pin "2") (pinfunction "2_2") (pintype "bidirectional"))
      (node (ref "TPB21") (pin "1") (pinfunction "1_1") (pintype "bidirectional"))
      (node (ref "U12") (pin "E21") (pinfunction "AON_IO_VCC_E21") (pintype "bidirectional"))
      (node (ref "U12") (pin "H22") (pinfunction "CMP_3P3_VCC_H22") (pintype "bidirectional"))
      (node (ref "U12") (pin "H24") (pinfunction "VDD_BLE_SEN_H24") (pintype "bidirectional"))
      (node (ref "U12") (pin "K2") (pinfunction "BUCK_VSEL_K2") (pintype "bidirectional"))
      (node (ref "U16") (pin "5") (pinfunction "VCC_5") (pintype "bidirectional"))
      (node (ref "U201") (pin "7") (pinfunction "HOLD_7") (pintype "bidirectional"))
      (node (ref "U201") (pin "8") (pinfunction "VCC_8") (pintype "bidirectional"))
    )
    (net (code "111") (name "VDD_PLAT_3P3_R") (class "Default")
      (node (ref "C20") (pin "1") (pinfunction "1_1") (pintype "bidirectional"))
      (node (ref "R35") (pin "1") (pinfunction "1_1") (pintype "bidirectional"))
      (node (ref "U12") (pin "G22") (pinfunction "COMP_AREF_G22") (pintype "bidirectional"))
      (node (ref "U12") (pin "H23") (pinfunction "ADC_3P3_VCC_H23") (pintype "bidirectional"))
    )
    (net (code "112") (name "VDD_SYS_3P3") (class "Default")
      (node (ref "R58") (pin "1") (pinfunction "1_1") (pintype "bidirectional"))
      (node (ref "R63") (pin "1") (pinfunction "1_1") (pintype "bidirectional"))
      (node (ref "R92") (pin "1") (pinfunction "1_1") (pintype "bidirectional"))
      (node (ref "U203") (pin "3") (pinfunction "VOUT_3") (pintype "bidirectional"))
    )
    (net (code "113") (name "VSYS") (class "Default")
      (node (ref "C25") (pin "1") (pinfunction "1_1") (pintype "bidirectional"))
      (node (ref "C26") (pin "1") (pinfunction "1_1") (pintype "bidirectional"))
      (node (ref "C31") (pin "1") (pinfunction "1_1") (pintype "bidirectional"))
      (node (ref "C32") (pin "1") (pinfunction "1_1") (pintype "bidirectional"))
      (node (ref "C33") (pin "1") (pinfunction "1_1") (pintype "bidirectional"))
      (node (ref "R63") (pin "2") (pinfunction "2_2") (pintype "bidirectional"))
      (node (ref "U12") (pin "L4") (pinfunction "VSYS_L4") (pintype "bidirectional"))
      (node (ref "U12") (pin "N4") (pinfunction "ESR2_VBATT_N4") (pintype "bidirectional"))
      (node (ref "U12") (pin "P2") (pinfunction "ESR1_VBATT_P2") (pintype "bidirectional"))
    )
    (net (code "114") (name "V_1P8_ESR3") (class "Default")
      (node (ref "C29") (pin "1") (pinfunction "1_1") (pintype "bidirectional"))
      (node (ref "C30") (pin "1") (pinfunction "1_1") (pintype "bidirectional"))
      (node (ref "L12") (pin "2") (pinfunction "2_2") (pintype "bidirectional"))
      (node (ref "U12") (pin "P3") (pinfunction "VDD_HOST_1P8_P3") (pintype "bidirectional"))
    )
    (net (code "115") (name "V_3P3SRC_VDD1") (class "Default")
      (node (ref "C13") (pin "1") (pinfunction "1_1") (pintype "bidirectional"))
      (node (ref "C56") (pin "1") (pinfunction "1_1") (pintype "bidirectional"))
      (node (ref "C57") (pin "1") (pinfunction "1_1") (pintype "bidirectional"))
      (node (ref "L14") (pin "2") (pinfunction "2_2") (pintype "bidirectional"))
      (node (ref "R90") (pin "2") (pinfunction "2_2") (pintype "bidirectional"))
      (node (ref "U203") (pin "2") (pinfunction "VIN_2") (pintype "bidirectional"))
      (node (ref "U204") (pin "1") (pinfunction "VDD_1") (pintype "bidirectional"))
      (node (ref "U204") (pin "9") (pinfunction "PG_N_9") (pintype "bidirectional"))
      (node (ref "U205") (pin "6") (pinfunction "VOS_6") (pintype "bidirectional"))
    )
    (net (code "116") (name "V_3P5_VREFA") (class "Default")
      (node (ref "C43") (pin "1") (pinfunction "1_1") (pintype "bidirectional"))
      (node (ref "R33") (pin "1") (pinfunction "1_1") (pintype "bidirectional"))
      (node (ref "R34") (pin "2") (pinfunction "2_2") (pintype "bidirectional"))
      (node (ref "U11") (pin "2") (pinfunction "VREF_A_2") (pintype "bidirectional"))
      (node (ref "U14") (pin "2") (pinfunction "VREF_A_2") (pintype "bidirectional"))
      (node (ref "U15") (pin "2") (pinfunction "VREF_A_2") (pintype "bidirectional"))
    )
    (net (code "117") (name "V_5P00SRC_SW_VDD1") (class "Default")
      (node (ref "C58") (pin "1") (pinfunction "1_1") (pintype "bidirectional"))
      (node (ref "J10") (pin "5") (pinfunction "P$5_5") (pintype "bidirectional"))
      (node (ref "J12") (pin "2") (pinfunction "P$2_2") (pintype "bidirectional"))
      (node (ref "R27") (pin "2") (pinfunction "2_2") (pintype "bidirectional"))
      (node (ref "R28") (pin "2") (pinfunction "2_2") (pintype "bidirectional"))
      (node (ref "R29") (pin "2") (pinfunction "2_2") (pintype "bidirectional"))
      (node (ref "R33") (pin "2") (pinfunction "2_2") (pintype "bidirectional"))
      (node (ref "R93") (pin "2") (pinfunction "2_2") (pintype "bidirectional"))
      (node (ref "U206") (pin "3") (pinfunction "VOUT_3") (pintype "bidirectional"))
    )
    (net (code "118") (name "V_5P00SRC_VDD1") (class "Default")
      (node (ref "C11") (pin "1") (pinfunction "1_1") (pintype "bidirectional"))
      (node (ref "C14") (pin "1") (pinfunction "1_1") (pintype "bidirectional"))
      (node (ref "C39") (pin "1") (pinfunction "1_1") (pintype "bidirectional"))
      (node (ref "C49") (pin "1") (pinfunction "1_1") (pintype "bidirectional"))
      (node (ref "L10") (pin "2") (pinfunction "2_2") (pintype "bidirectional"))
      (node (ref "R57") (pin "1") (pinfunction "1_1") (pintype "bidirectional"))
      (node (ref "R70") (pin "1") (pinfunction "1_1") (pintype "bidirectional"))
      (node (ref "R89") (pin "1") (pinfunction "1_1") (pintype "bidirectional"))
      (node (ref "R93") (pin "1") (pinfunction "1_1") (pintype "bidirectional"))
      (node (ref "U10") (pin "14") (pinfunction "VOS_14") (pintype "bidirectional"))
      (node (ref "U13") (pin "1") (pinfunction "VOUT1_1") (pintype "bidirectional"))
      (node (ref "U13") (pin "4") (pinfunction "VOUT2_4") (pintype "bidirectional"))
      (node (ref "U205") (pin "2") (pinfunction "VIN_2") (pintype "bidirectional"))
      (node (ref "U206") (pin "2") (pinfunction "VIN_2") (pintype "bidirectional"))
    )
    (net (code "119") (name "unconnected-(J15-P$7-Pad7)") (class "Default")
      (node (ref "J15") (pin "7") (pinfunction "P$7_7") (pintype "bidirectional"))
    )
    (net (code "120") (name "unconnected-(U$1-Pad1)") (class "Default")
      (node (ref "U$1") (pin "1") (pinfunction "1_1") (pintype "no_connect"))
    )
    (net (code "121") (name "unconnected-(U$2-Pad1)") (class "Default")
      (node (ref "U$2") (pin "1") (pinfunction "1_1") (pintype "no_connect"))
    )
    (net (code "122") (name "unconnected-(U$3-Pad1)") (class "Default")
      (node (ref "U$3") (pin "1") (pinfunction "1_1") (pintype "no_connect"))
    )
    (net (code "123") (name "unconnected-(U$4-Pad1)") (class "Default")
      (node (ref "U$4") (pin "1") (pinfunction "1_1") (pintype "no_connect"))
    )
    (net (code "124") (name "unconnected-(U10-PG-Pad4)") (class "Default")
      (node (ref "U10") (pin "4") (pinfunction "PG_4") (pintype "bidirectional"))
    )
    (net (code "125") (name "unconnected-(U12A-ESR1_LX-PadN1)") (class "Default")
      (node (ref "U12") (pin "N1") (pinfunction "ESR1_LX_N1") (pintype "bidirectional"))
    )
    (net (code "126") (name "unconnected-(U12A-ESR2_LX-PadM4)") (class "Default")
      (node (ref "U12") (pin "M4") (pinfunction "ESR2_LX_M4") (pintype "bidirectional"))
    )
    (net (code "127") (name "unconnected-(U12B-BLE_DEC2-PadG23)") (class "Default")
      (node (ref "U12") (pin "G23") (pinfunction "BLE_DEC2_G23") (pintype "bidirectional"))
    )
    (net (code "128") (name "unconnected-(U12B-BLE_SCL-PadF23)") (class "Default")
      (node (ref "U12") (pin "F23") (pinfunction "BLE_SCL_F23") (pintype "bidirectional"))
    )
    (net (code "129") (name "unconnected-(U12B-BLE_SDA-PadB23)") (class "Default")
      (node (ref "U12") (pin "B23") (pinfunction "BLE_SDA_B23") (pintype "bidirectional"))
    )
    (net (code "130") (name "unconnected-(U12B-BT_GPIO-PadB24)") (class "Default")
      (node (ref "U12") (pin "B24") (pinfunction "BT_GPIO_B24") (pintype "bidirectional"))
    )
    (net (code "131") (name "unconnected-(U12C-BATT_TEMP-PadN22)") (class "Default")
      (node (ref "U12") (pin "N22") (pinfunction "BATT_TEMP_N22") (pintype "bidirectional"))
    )
    (net (code "132") (name "unconnected-(U12C-CHG_STATUS-PadM22)") (class "Default")
      (node (ref "U12") (pin "M22") (pinfunction "CHG_STATUS_M22") (pintype "bidirectional"))
    )
    (net (code "133") (name "unconnected-(U12C-SW_FG_VBATT-PadP21)") (class "Default")
      (node (ref "U12") (pin "P21") (pinfunction "SW_FG_VBATT_P21") (pintype "bidirectional"))
    )
    (net (code "134") (name "unconnected-(U12E-ATP_INT1-PadN3)") (class "Default")
      (node (ref "U12") (pin "N3") (pinfunction "ATP_INT1_N3") (pintype "bidirectional"))
    )
    (net (code "135") (name "unconnected-(U12E-ATP_INT2-PadL3)") (class "Default")
      (node (ref "U12") (pin "L3") (pinfunction "ATP_INT2_L3") (pintype "bidirectional"))
    )
    (net (code "136") (name "unconnected-(U12E-ATP_INT3-PadF21)") (class "Default")
      (node (ref "U12") (pin "F21") (pinfunction "ATP_INT3_F21") (pintype "bidirectional"))
    )
    (net (code "137") (name "unconnected-(U12E-SPI0_SS_CS0-PadH4)") (class "Default")
      (node (ref "U12") (pin "H4") (pinfunction "SPI0_SS_CS0_H4") (pintype "bidirectional"))
    )
    (net (code "138") (name "unconnected-(U12E-SPI0_SS_CS1-PadH3)") (class "Default")
      (node (ref "U12") (pin "H3") (pinfunction "SPI0_SS_CS1_H3") (pintype "bidirectional"))
    )
    (net (code "139") (name "unconnected-(U12E-SPI0_SS_CS2-PadK3)") (class "Default")
      (node (ref "U12") (pin "K3") (pinfunction "SPI0_SS_CS2_K3") (pintype "bidirectional"))
    )
    (net (code "140") (name "unconnected-(U12E-SPI0_SS_CS3-PadG4)") (class "Default")
      (node (ref "U12") (pin "G4") (pinfunction "SPI0_SS_CS3_G4") (pintype "bidirectional"))
    )
    (net (code "141") (name "unconnected-(U12E-SPI0_SS_MISO-PadJ3)") (class "Default")
      (node (ref "U12") (pin "J3") (pinfunction "SPI0_SS_MISO_J3") (pintype "bidirectional"))
    )
    (net (code "142") (name "unconnected-(U12E-SPI0_SS_MOSI-PadM3)") (class "Default")
      (node (ref "U12") (pin "M3") (pinfunction "SPI0_SS_MOSI_M3") (pintype "bidirectional"))
    )
    (net (code "143") (name "unconnected-(U12E-SPI0_SS_SCK-PadJ4)") (class "Default")
      (node (ref "U12") (pin "J4") (pinfunction "SPI0_SS_SCK_J4") (pintype "bidirectional"))
    )
    (net (code "144") (name "unconnected-(U12E-SPI1_M_CS2-PadB21)") (class "Default")
      (node (ref "U12") (pin "B21") (pinfunction "SPI1_M_CS2_B21") (pintype "bidirectional"))
    )
    (net (code "145") (name "unconnected-(U12E-SPI1_M_CS3-PadC22)") (class "Default")
      (node (ref "U12") (pin "C22") (pinfunction "SPI1_M_CS3_C22") (pintype "bidirectional"))
    )
    (net (code "146") (name "unconnected-(U12F-6AXIS_INT2-PadA23)") (class "Default")
      (node (ref "U12") (pin "A23") (pinfunction "6AXIS_INT2_A23") (pintype "bidirectional"))
    )
    (net (code "147") (name "unconnected-(U12F-6AXIS_SCL-PadA22)") (class "Default")
      (node (ref "U12") (pin "A22") (pinfunction "6AXIS_SCL_A22") (pintype "bidirectional"))
    )
    (net (code "148") (name "unconnected-(U12F-6AXIS_SDA-PadA21)") (class "Default")
      (node (ref "U12") (pin "A21") (pinfunction "6AXIS_SDA_A21") (pintype "bidirectional"))
    )
    (net (code "149") (name "unconnected-(U12F-I2C0_SCL-PadM24)") (class "Default")
      (node (ref "U12") (pin "M24") (pinfunction "I2C0_SCL_M24") (pintype "bidirectional"))
    )
    (net (code "150") (name "unconnected-(U12F-I2C0_SDA-PadP23)") (class "Default")
      (node (ref "U12") (pin "P23") (pinfunction "I2C0_SDA_P23") (pintype "bidirectional"))
    )
    (net (code "151") (name "unconnected-(U12F-I2C1_SCL-PadE1)") (class "Default")
      (node (ref "U12") (pin "E1") (pinfunction "I2C1_SCL_E1") (pintype "bidirectional"))
    )
    (net (code "152") (name "unconnected-(U12F-I2C1_SDA-PadD2)") (class "Default")
      (node (ref "U12") (pin "D2") (pinfunction "I2C1_SDA_D2") (pintype "bidirectional"))
    )
    (net (code "153") (name "unconnected-(U12F-I2C1_SS_SCL-PadF1)") (class "Default")
      (node (ref "U12") (pin "F1") (pinfunction "I2C1_SS_SCL_F1") (pintype "bidirectional"))
    )
    (net (code "154") (name "unconnected-(U12F-I2C1_SS_SDA-PadE2)") (class "Default")
      (node (ref "U12") (pin "E2") (pinfunction "I2C1_SS_SDA_E2") (pintype "bidirectional"))
    )
    (net (code "155") (name "unconnected-(U13-OC_FLAG-Pad7)") (class "Default")
      (node (ref "U13") (pin "7") (pinfunction "OC_FLAG_7") (pintype "bidirectional"))
    )
    (net (code "156") (name "unconnected-(U15-A1-Pad3)") (class "Default")
      (node (ref "U15") (pin "3") (pinfunction "A1_3") (pintype "bidirectional"))
    )
    (net (code "157") (name "unconnected-(U15-A2-Pad4)") (class "Default")
      (node (ref "U15") (pin "4") (pinfunction "A2_4") (pintype "bidirectional"))
    )
    (net (code "158") (name "unconnected-(U15-B1-Pad18)") (class "Default")
      (node (ref "U15") (pin "18") (pinfunction "B1_18") (pintype "bidirectional"))
    )
    (net (code "159") (name "unconnected-(U15-B2-Pad17)") (class "Default")
      (node (ref "U15") (pin "17") (pinfunction "B2_17") (pintype "bidirectional"))
    )
    (net (code "160") (name "unconnected-(U16-NC-Pad1)") (class "Default")
      (node (ref "U16") (pin "1") (pinfunction "NC_1") (pintype "bidirectional"))
    )
    (net (code "161") (name "unconnected-(U202-C_DLY-Pad5)") (class "Default")
      (node (ref "U202") (pin "5") (pinfunction "C_DLY_5") (pintype "bidirectional"))
    )
    (net (code "162") (name "unconnected-(U204-EXIT_N_MON-Pad11)") (class "Default")
      (node (ref "U204") (pin "11") (pinfunction "EXIT_N_MON_11") (pintype "bidirectional"))
    )
    (net (code "163") (name "unconnected-(U204-HOST1P8_DIS-Pad7)") (class "Default")
      (node (ref "U204") (pin "7") (pinfunction "HOST1P8_DIS_7") (pintype "bidirectional"))
    )
    (net (code "164") (name "unconnected-(U204-NC-Pad6)") (class "Default")
      (node (ref "U204") (pin "6") (pinfunction "NC_6") (pintype "bidirectional"))
    )
    (net (code "165") (name "unconnected-(U204-NC_1-Pad13)") (class "Default")
      (node (ref "U204") (pin "13") (pinfunction "NC_1_13") (pintype "bidirectional"))
    )
    (net (code "166") (name "unconnected-(U204-SHIP_MODE_EN-Pad5)") (class "Default")
      (node (ref "U204") (pin "5") (pinfunction "SHIP_MODE_EN_5") (pintype "bidirectional"))
    )
    (net (code "167") (name "unconnected-(U204-SHIP_MODE_EXIT-Pad3)") (class "Default")
      (node (ref "U204") (pin "3") (pinfunction "SHIP_MODE_EXIT_3") (pintype "bidirectional"))
    )
    (net (code "168") (name "unconnected-(U204-SHIP_MODE_EXIT_N-Pad2)") (class "Default")
      (node (ref "U204") (pin "2") (pinfunction "SHIP_MODE_EXIT_N_2") (pintype "bidirectional"))
    )
  )
)
